# altair.net
KiCad netlist of a schematic drawn in EAGLE
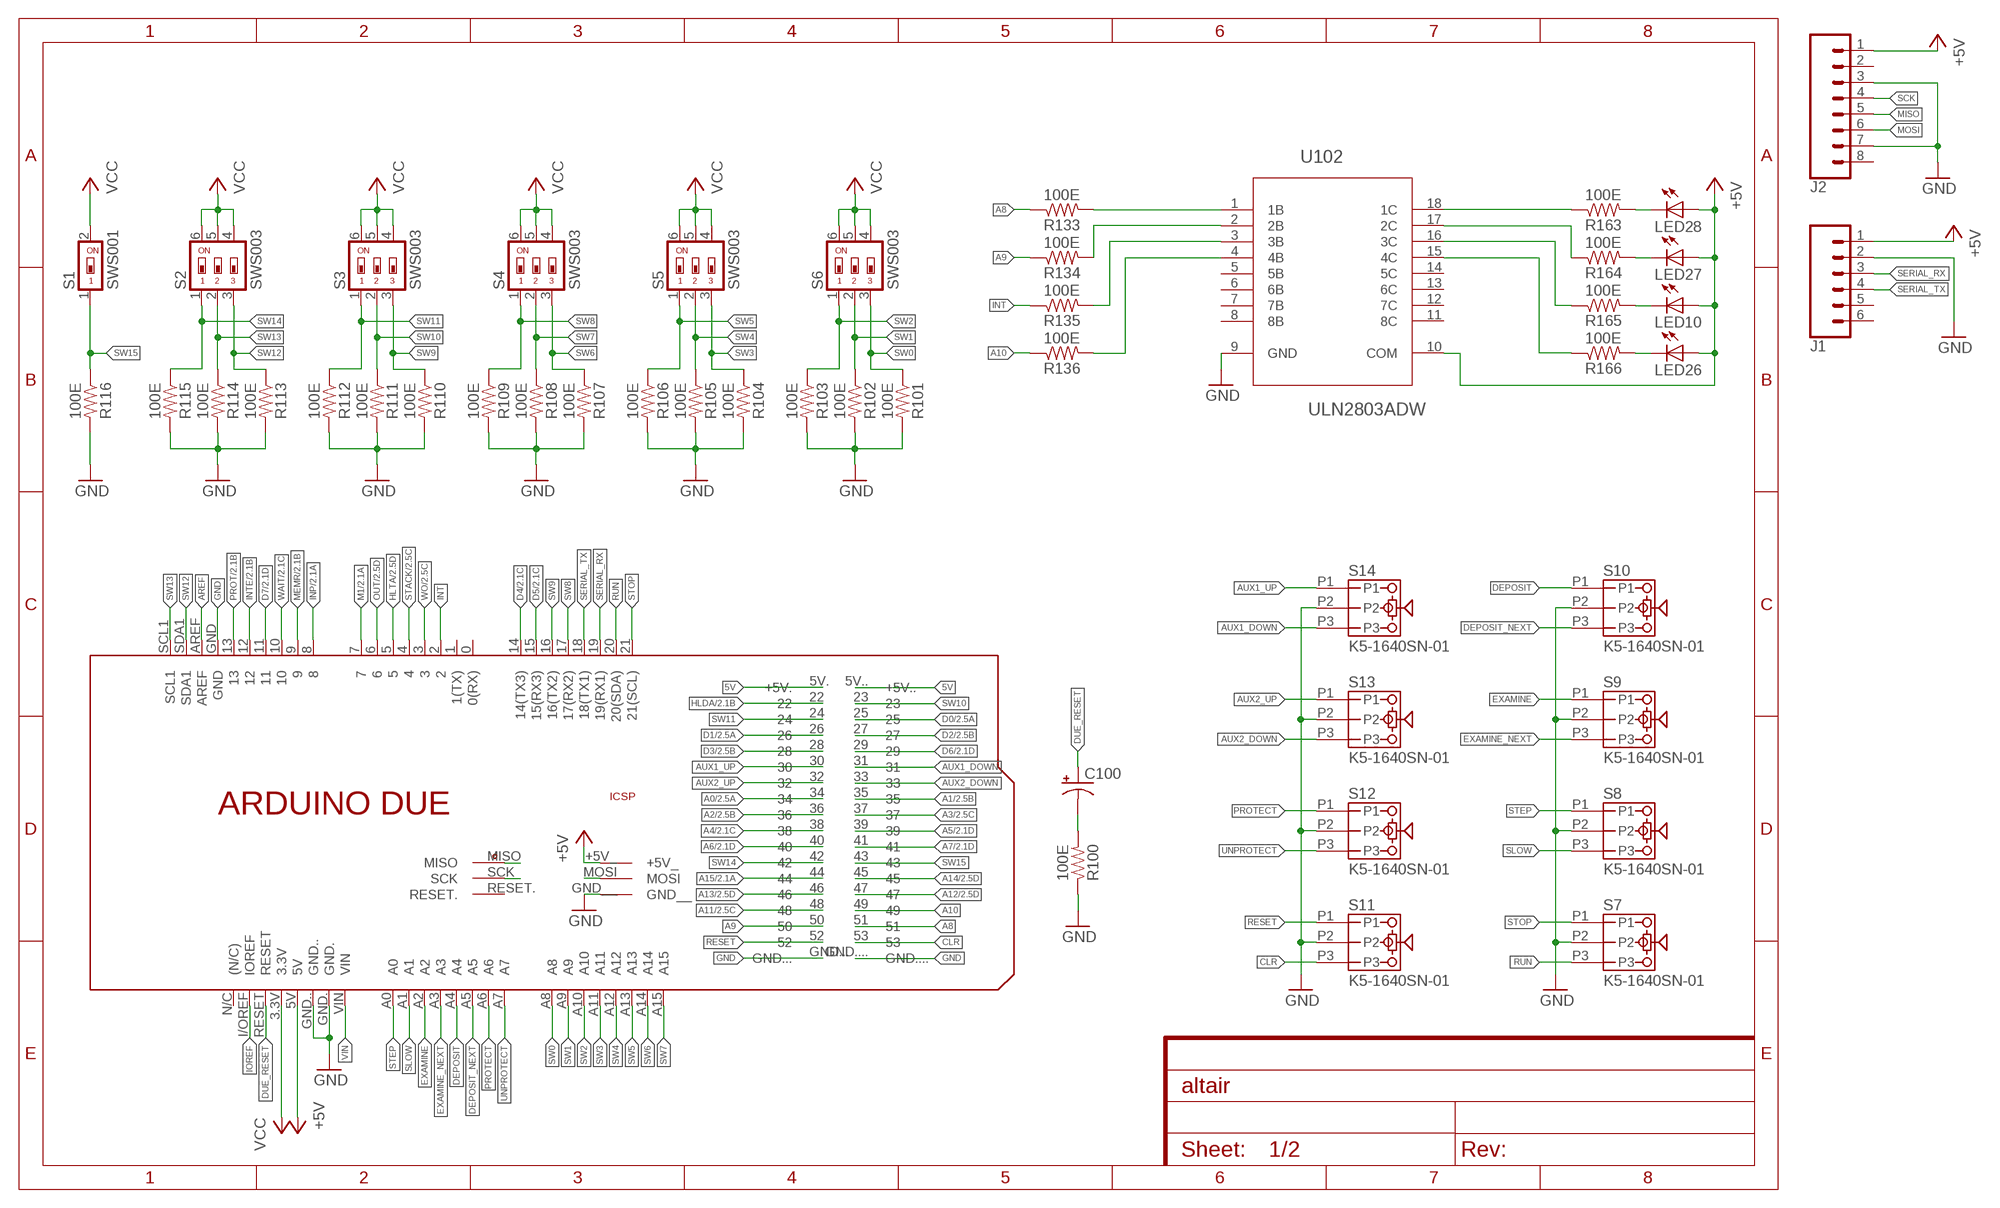
[diagram p0: schematic, sheet 1]
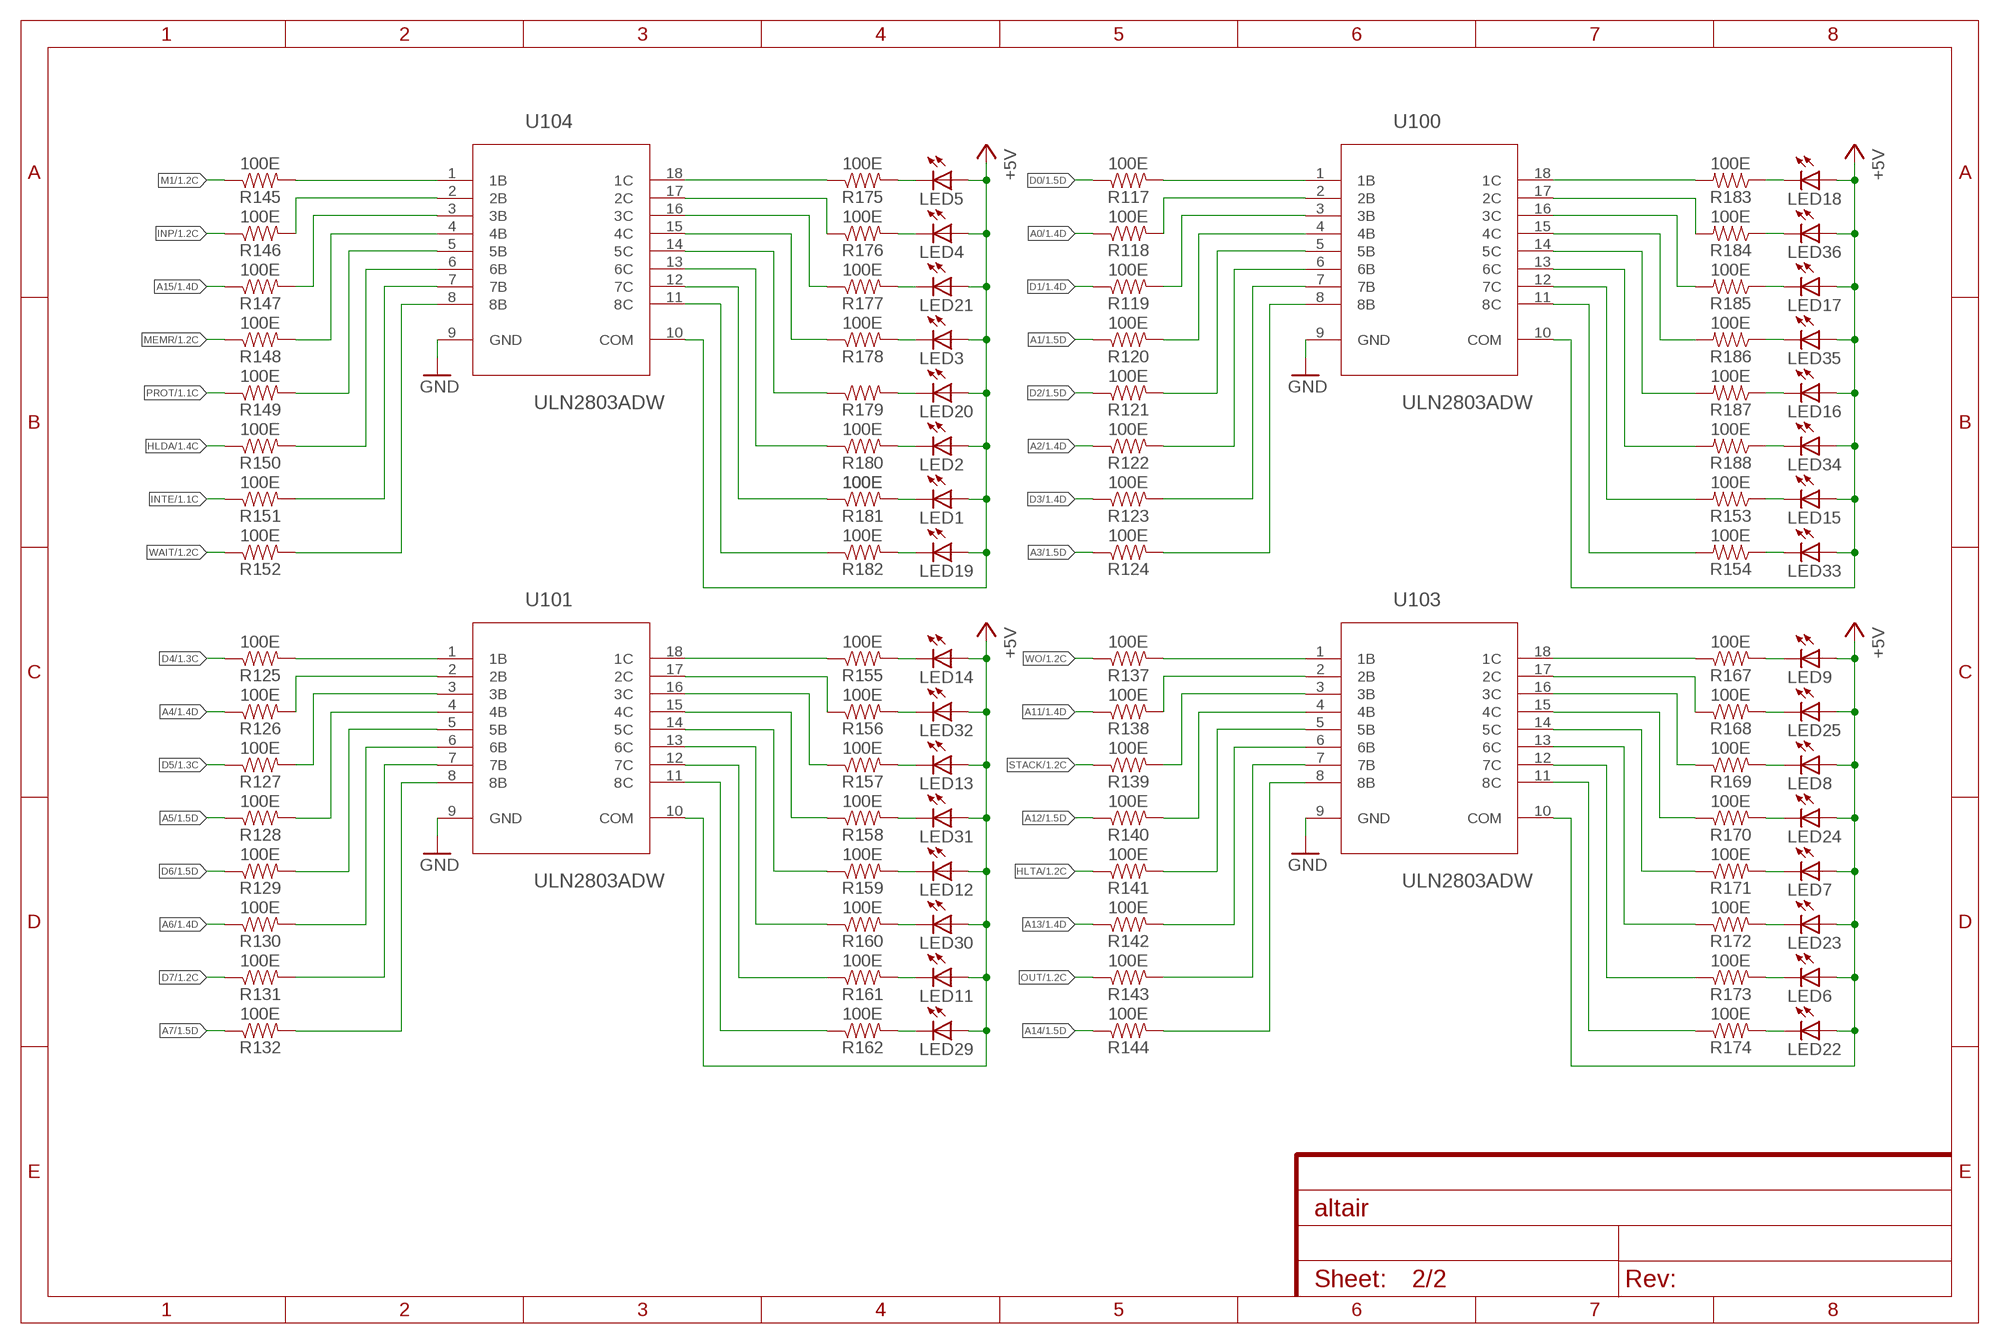
[diagram p1: schematic, sheet 2]

(export (version "E")
  (design (tool "Eeschema 10.0.6"))
  (components
    (comp (ref "C100")
      (value "CPOL-USD")
      (footprint "eagle-import:PANASONIC_D")
      (libsource (lib "eagle-import") (part "CPOL-USD"))
    )
    (comp (ref "J1")
      (value "CONN_06LOCK")
      (footprint "eagle-import:1X06_LOCK")
      (libsource (lib "eagle-import") (part "CONN_06LOCK"))
    )
    (comp (ref "J2")
      (value "CONN_08LOCK")
      (footprint "eagle-import:1X08_LOCK")
      (libsource (lib "eagle-import") (part "CONN_08LOCK"))
    )
    (comp (ref "LED10")
      (value "LEDCHIP-LED0805")
      (footprint "eagle-import:CHIP-LED0805")
      (libsource (lib "eagle-import") (part "LEDCHIP-LED0805"))
    )
    (comp (ref "LED26")
      (value "LEDCHIP-LED0805")
      (footprint "eagle-import:CHIP-LED0805")
      (libsource (lib "eagle-import") (part "LEDCHIP-LED0805"))
    )
    (comp (ref "LED27")
      (value "LEDCHIP-LED0805")
      (footprint "eagle-import:CHIP-LED0805")
      (libsource (lib "eagle-import") (part "LEDCHIP-LED0805"))
    )
    (comp (ref "LED28")
      (value "LEDCHIP-LED0805")
      (footprint "eagle-import:CHIP-LED0805")
      (libsource (lib "eagle-import") (part "LEDCHIP-LED0805"))
    )
    (comp (ref "PCB1")
      (value "ARDUINO_DUEARDUINO_DUE")
      (footprint "eagle-import:ARDUINO_MEGA2560")
      (libsource (lib "eagle-import") (part "ARDUINO_DUEARDUINO_DUE"))
    )
    (comp (ref "R100")
      (value "100E")
      (footprint "eagle-import:0805")
      (libsource (lib "eagle-import") (part "RESISTOR0805"))
    )
    (comp (ref "R101")
      (value "100E")
      (footprint "eagle-import:0805")
      (libsource (lib "eagle-import") (part "RESISTOR0805"))
    )
    (comp (ref "R102")
      (value "100E")
      (footprint "eagle-import:0805")
      (libsource (lib "eagle-import") (part "RESISTOR0805"))
    )
    (comp (ref "R103")
      (value "100E")
      (footprint "eagle-import:0805")
      (libsource (lib "eagle-import") (part "RESISTOR0805"))
    )
    (comp (ref "R104")
      (value "100E")
      (footprint "eagle-import:0805")
      (libsource (lib "eagle-import") (part "RESISTOR0805"))
    )
    (comp (ref "R105")
      (value "100E")
      (footprint "eagle-import:0805")
      (libsource (lib "eagle-import") (part "RESISTOR0805"))
    )
    (comp (ref "R106")
      (value "100E")
      (footprint "eagle-import:0805")
      (libsource (lib "eagle-import") (part "RESISTOR0805"))
    )
    (comp (ref "R107")
      (value "100E")
      (footprint "eagle-import:0805")
      (libsource (lib "eagle-import") (part "RESISTOR0805"))
    )
    (comp (ref "R108")
      (value "100E")
      (footprint "eagle-import:0805")
      (libsource (lib "eagle-import") (part "RESISTOR0805"))
    )
    (comp (ref "R109")
      (value "100E")
      (footprint "eagle-import:0805")
      (libsource (lib "eagle-import") (part "RESISTOR0805"))
    )
    (comp (ref "R110")
      (value "100E")
      (footprint "eagle-import:0805")
      (libsource (lib "eagle-import") (part "RESISTOR0805"))
    )
    (comp (ref "R111")
      (value "100E")
      (footprint "eagle-import:0805")
      (libsource (lib "eagle-import") (part "RESISTOR0805"))
    )
    (comp (ref "R112")
      (value "100E")
      (footprint "eagle-import:0805")
      (libsource (lib "eagle-import") (part "RESISTOR0805"))
    )
    (comp (ref "R113")
      (value "100E")
      (footprint "eagle-import:0805")
      (libsource (lib "eagle-import") (part "RESISTOR0805"))
    )
    (comp (ref "R114")
      (value "100E")
      (footprint "eagle-import:0805")
      (libsource (lib "eagle-import") (part "RESISTOR0805"))
    )
    (comp (ref "R115")
      (value "100E")
      (footprint "eagle-import:0805")
      (libsource (lib "eagle-import") (part "RESISTOR0805"))
    )
    (comp (ref "R116")
      (value "100E")
      (footprint "eagle-import:0805")
      (libsource (lib "eagle-import") (part "RESISTOR0805"))
    )
    (comp (ref "R133")
      (value "100E")
      (footprint "eagle-import:0805")
      (libsource (lib "eagle-import") (part "RESISTOR0805"))
    )
    (comp (ref "R134")
      (value "100E")
      (footprint "eagle-import:0805")
      (libsource (lib "eagle-import") (part "RESISTOR0805"))
    )
    (comp (ref "R135")
      (value "100E")
      (footprint "eagle-import:0805")
      (libsource (lib "eagle-import") (part "RESISTOR0805"))
    )
    (comp (ref "R136")
      (value "100E")
      (footprint "eagle-import:0805")
      (libsource (lib "eagle-import") (part "RESISTOR0805"))
    )
    (comp (ref "R163")
      (value "100E")
      (footprint "eagle-import:0805")
      (libsource (lib "eagle-import") (part "RESISTOR0805"))
    )
    (comp (ref "R164")
      (value "100E")
      (footprint "eagle-import:0805")
      (libsource (lib "eagle-import") (part "RESISTOR0805"))
    )
    (comp (ref "R165")
      (value "100E")
      (footprint "eagle-import:0805")
      (libsource (lib "eagle-import") (part "RESISTOR0805"))
    )
    (comp (ref "R166")
      (value "100E")
      (footprint "eagle-import:0805")
      (libsource (lib "eagle-import") (part "RESISTOR0805"))
    )
    (comp (ref "S1")
      (value "SWS001")
      (footprint "eagle-import:SMS-001")
      (libsource (lib "eagle-import") (part "SWS001"))
    )
    (comp (ref "S2")
      (value "SWS003")
      (footprint "eagle-import:SMS-003")
      (libsource (lib "eagle-import") (part "SWS003"))
    )
    (comp (ref "S3")
      (value "SWS003")
      (footprint "eagle-import:SMS-003")
      (libsource (lib "eagle-import") (part "SWS003"))
    )
    (comp (ref "S4")
      (value "SWS003")
      (footprint "eagle-import:SMS-003")
      (libsource (lib "eagle-import") (part "SWS003"))
    )
    (comp (ref "S5")
      (value "SWS003")
      (footprint "eagle-import:SMS-003")
      (libsource (lib "eagle-import") (part "SWS003"))
    )
    (comp (ref "S6")
      (value "SWS003")
      (footprint "eagle-import:SMS-003")
      (libsource (lib "eagle-import") (part "SWS003"))
    )
    (comp (ref "S7")
      (value "K5-1640SN-01")
      (footprint "eagle-import:K5-1640SN-01")
      (libsource (lib "eagle-import") (part "K5-1640SN-01"))
    )
    (comp (ref "S8")
      (value "K5-1640SN-01")
      (footprint "eagle-import:K5-1640SN-01")
      (libsource (lib "eagle-import") (part "K5-1640SN-01"))
    )
    (comp (ref "S9")
      (value "K5-1640SN-01")
      (footprint "eagle-import:K5-1640SN-01")
      (libsource (lib "eagle-import") (part "K5-1640SN-01"))
    )
    (comp (ref "S10")
      (value "K5-1640SN-01")
      (footprint "eagle-import:K5-1640SN-01")
      (libsource (lib "eagle-import") (part "K5-1640SN-01"))
    )
    (comp (ref "S11")
      (value "K5-1640SN-01")
      (footprint "eagle-import:K5-1640SN-01")
      (libsource (lib "eagle-import") (part "K5-1640SN-01"))
    )
    (comp (ref "S12")
      (value "K5-1640SN-01")
      (footprint "eagle-import:K5-1640SN-01")
      (libsource (lib "eagle-import") (part "K5-1640SN-01"))
    )
    (comp (ref "S13")
      (value "K5-1640SN-01")
      (footprint "eagle-import:K5-1640SN-01")
      (libsource (lib "eagle-import") (part "K5-1640SN-01"))
    )
    (comp (ref "S14")
      (value "K5-1640SN-01")
      (footprint "eagle-import:K5-1640SN-01")
      (libsource (lib "eagle-import") (part "K5-1640SN-01"))
    )
    (comp (ref "U102")
      (value "ULN2803ADW")
      (footprint "eagle-import:SOIC127P1030X265-18N")
      (libsource (lib "eagle-import") (part "ULN2803ADW"))
    )
    (comp (ref "LED1")
      (value "LEDCHIP-LED0805")
      (footprint "eagle-import:CHIP-LED0805")
      (libsource (lib "eagle-import") (part "LEDCHIP-LED0805"))
    )
    (comp (ref "LED2")
      (value "LEDCHIP-LED0805")
      (footprint "eagle-import:CHIP-LED0805")
      (libsource (lib "eagle-import") (part "LEDCHIP-LED0805"))
    )
    (comp (ref "LED3")
      (value "LEDCHIP-LED0805")
      (footprint "eagle-import:CHIP-LED0805")
      (libsource (lib "eagle-import") (part "LEDCHIP-LED0805"))
    )
    (comp (ref "LED4")
      (value "LEDCHIP-LED0805")
      (footprint "eagle-import:CHIP-LED0805")
      (libsource (lib "eagle-import") (part "LEDCHIP-LED0805"))
    )
    (comp (ref "LED5")
      (value "LEDCHIP-LED0805")
      (footprint "eagle-import:CHIP-LED0805")
      (libsource (lib "eagle-import") (part "LEDCHIP-LED0805"))
    )
    (comp (ref "LED6")
      (value "LEDCHIP-LED0805")
      (footprint "eagle-import:CHIP-LED0805")
      (libsource (lib "eagle-import") (part "LEDCHIP-LED0805"))
    )
    (comp (ref "LED7")
      (value "LEDCHIP-LED0805")
      (footprint "eagle-import:CHIP-LED0805")
      (libsource (lib "eagle-import") (part "LEDCHIP-LED0805"))
    )
    (comp (ref "LED8")
      (value "LEDCHIP-LED0805")
      (footprint "eagle-import:CHIP-LED0805")
      (libsource (lib "eagle-import") (part "LEDCHIP-LED0805"))
    )
    (comp (ref "LED9")
      (value "LEDCHIP-LED0805")
      (footprint "eagle-import:CHIP-LED0805")
      (libsource (lib "eagle-import") (part "LEDCHIP-LED0805"))
    )
    (comp (ref "LED11")
      (value "LEDCHIP-LED0805")
      (footprint "eagle-import:CHIP-LED0805")
      (libsource (lib "eagle-import") (part "LEDCHIP-LED0805"))
    )
    (comp (ref "LED12")
      (value "LEDCHIP-LED0805")
      (footprint "eagle-import:CHIP-LED0805")
      (libsource (lib "eagle-import") (part "LEDCHIP-LED0805"))
    )
    (comp (ref "LED13")
      (value "LEDCHIP-LED0805")
      (footprint "eagle-import:CHIP-LED0805")
      (libsource (lib "eagle-import") (part "LEDCHIP-LED0805"))
    )
    (comp (ref "LED14")
      (value "LEDCHIP-LED0805")
      (footprint "eagle-import:CHIP-LED0805")
      (libsource (lib "eagle-import") (part "LEDCHIP-LED0805"))
    )
    (comp (ref "LED15")
      (value "LEDCHIP-LED0805")
      (footprint "eagle-import:CHIP-LED0805")
      (libsource (lib "eagle-import") (part "LEDCHIP-LED0805"))
    )
    (comp (ref "LED16")
      (value "LEDCHIP-LED0805")
      (footprint "eagle-import:CHIP-LED0805")
      (libsource (lib "eagle-import") (part "LEDCHIP-LED0805"))
    )
    (comp (ref "LED17")
      (value "LEDCHIP-LED0805")
      (footprint "eagle-import:CHIP-LED0805")
      (libsource (lib "eagle-import") (part "LEDCHIP-LED0805"))
    )
    (comp (ref "LED18")
      (value "LEDCHIP-LED0805")
      (footprint "eagle-import:CHIP-LED0805")
      (libsource (lib "eagle-import") (part "LEDCHIP-LED0805"))
    )
    (comp (ref "LED19")
      (value "LEDCHIP-LED0805")
      (footprint "eagle-import:CHIP-LED0805")
      (libsource (lib "eagle-import") (part "LEDCHIP-LED0805"))
    )
    (comp (ref "LED20")
      (value "LEDCHIP-LED0805")
      (footprint "eagle-import:CHIP-LED0805")
      (libsource (lib "eagle-import") (part "LEDCHIP-LED0805"))
    )
    (comp (ref "LED21")
      (value "LEDCHIP-LED0805")
      (footprint "eagle-import:CHIP-LED0805")
      (libsource (lib "eagle-import") (part "LEDCHIP-LED0805"))
    )
    (comp (ref "LED22")
      (value "LEDCHIP-LED0805")
      (footprint "eagle-import:CHIP-LED0805")
      (libsource (lib "eagle-import") (part "LEDCHIP-LED0805"))
    )
    (comp (ref "LED23")
      (value "LEDCHIP-LED0805")
      (footprint "eagle-import:CHIP-LED0805")
      (libsource (lib "eagle-import") (part "LEDCHIP-LED0805"))
    )
    (comp (ref "LED24")
      (value "LEDCHIP-LED0805")
      (footprint "eagle-import:CHIP-LED0805")
      (libsource (lib "eagle-import") (part "LEDCHIP-LED0805"))
    )
    (comp (ref "LED25")
      (value "LEDCHIP-LED0805")
      (footprint "eagle-import:CHIP-LED0805")
      (libsource (lib "eagle-import") (part "LEDCHIP-LED0805"))
    )
    (comp (ref "LED29")
      (value "LEDCHIP-LED0805")
      (footprint "eagle-import:CHIP-LED0805")
      (libsource (lib "eagle-import") (part "LEDCHIP-LED0805"))
    )
    (comp (ref "LED30")
      (value "LEDCHIP-LED0805")
      (footprint "eagle-import:CHIP-LED0805")
      (libsource (lib "eagle-import") (part "LEDCHIP-LED0805"))
    )
    (comp (ref "LED31")
      (value "LEDCHIP-LED0805")
      (footprint "eagle-import:CHIP-LED0805")
      (libsource (lib "eagle-import") (part "LEDCHIP-LED0805"))
    )
    (comp (ref "LED32")
      (value "LEDCHIP-LED0805")
      (footprint "eagle-import:CHIP-LED0805")
      (libsource (lib "eagle-import") (part "LEDCHIP-LED0805"))
    )
    (comp (ref "LED33")
      (value "LEDCHIP-LED0805")
      (footprint "eagle-import:CHIP-LED0805")
      (libsource (lib "eagle-import") (part "LEDCHIP-LED0805"))
    )
    (comp (ref "LED34")
      (value "LEDCHIP-LED0805")
      (footprint "eagle-import:CHIP-LED0805")
      (libsource (lib "eagle-import") (part "LEDCHIP-LED0805"))
    )
    (comp (ref "LED35")
      (value "LEDCHIP-LED0805")
      (footprint "eagle-import:CHIP-LED0805")
      (libsource (lib "eagle-import") (part "LEDCHIP-LED0805"))
    )
    (comp (ref "LED36")
      (value "LEDCHIP-LED0805")
      (footprint "eagle-import:CHIP-LED0805")
      (libsource (lib "eagle-import") (part "LEDCHIP-LED0805"))
    )
    (comp (ref "R117")
      (value "100E")
      (footprint "eagle-import:0805")
      (libsource (lib "eagle-import") (part "RESISTOR0805"))
    )
    (comp (ref "R118")
      (value "100E")
      (footprint "eagle-import:0805")
      (libsource (lib "eagle-import") (part "RESISTOR0805"))
    )
    (comp (ref "R119")
      (value "100E")
      (footprint "eagle-import:0805")
      (libsource (lib "eagle-import") (part "RESISTOR0805"))
    )
    (comp (ref "R120")
      (value "100E")
      (footprint "eagle-import:0805")
      (libsource (lib "eagle-import") (part "RESISTOR0805"))
    )
    (comp (ref "R121")
      (value "100E")
      (footprint "eagle-import:0805")
      (libsource (lib "eagle-import") (part "RESISTOR0805"))
    )
    (comp (ref "R122")
      (value "100E")
      (footprint "eagle-import:0805")
      (libsource (lib "eagle-import") (part "RESISTOR0805"))
    )
    (comp (ref "R123")
      (value "100E")
      (footprint "eagle-import:0805")
      (libsource (lib "eagle-import") (part "RESISTOR0805"))
    )
    (comp (ref "R124")
      (value "100E")
      (footprint "eagle-import:0805")
      (libsource (lib "eagle-import") (part "RESISTOR0805"))
    )
    (comp (ref "R125")
      (value "100E")
      (footprint "eagle-import:0805")
      (libsource (lib "eagle-import") (part "RESISTOR0805"))
    )
    (comp (ref "R126")
      (value "100E")
      (footprint "eagle-import:0805")
      (libsource (lib "eagle-import") (part "RESISTOR0805"))
    )
    (comp (ref "R127")
      (value "100E")
      (footprint "eagle-import:0805")
      (libsource (lib "eagle-import") (part "RESISTOR0805"))
    )
    (comp (ref "R128")
      (value "100E")
      (footprint "eagle-import:0805")
      (libsource (lib "eagle-import") (part "RESISTOR0805"))
    )
    (comp (ref "R129")
      (value "100E")
      (footprint "eagle-import:0805")
      (libsource (lib "eagle-import") (part "RESISTOR0805"))
    )
    (comp (ref "R130")
      (value "100E")
      (footprint "eagle-import:0805")
      (libsource (lib "eagle-import") (part "RESISTOR0805"))
    )
    (comp (ref "R131")
      (value "100E")
      (footprint "eagle-import:0805")
      (libsource (lib "eagle-import") (part "RESISTOR0805"))
    )
    (comp (ref "R132")
      (value "100E")
      (footprint "eagle-import:0805")
      (libsource (lib "eagle-import") (part "RESISTOR0805"))
    )
    (comp (ref "R137")
      (value "100E")
      (footprint "eagle-import:0805")
      (libsource (lib "eagle-import") (part "RESISTOR0805"))
    )
    (comp (ref "R138")
      (value "100E")
      (footprint "eagle-import:0805")
      (libsource (lib "eagle-import") (part "RESISTOR0805"))
    )
    (comp (ref "R139")
      (value "100E")
      (footprint "eagle-import:0805")
      (libsource (lib "eagle-import") (part "RESISTOR0805"))
    )
    (comp (ref "R140")
      (value "100E")
      (footprint "eagle-import:0805")
      (libsource (lib "eagle-import") (part "RESISTOR0805"))
    )
    (comp (ref "R141")
      (value "100E")
      (footprint "eagle-import:0805")
      (libsource (lib "eagle-import") (part "RESISTOR0805"))
    )
    (comp (ref "R142")
      (value "100E")
      (footprint "eagle-import:0805")
      (libsource (lib "eagle-import") (part "RESISTOR0805"))
    )
    (comp (ref "R143")
      (value "100E")
      (footprint "eagle-import:0805")
      (libsource (lib "eagle-import") (part "RESISTOR0805"))
    )
    (comp (ref "R144")
      (value "100E")
      (footprint "eagle-import:0805")
      (libsource (lib "eagle-import") (part "RESISTOR0805"))
    )
    (comp (ref "R145")
      (value "100E")
      (footprint "eagle-import:0805")
      (libsource (lib "eagle-import") (part "RESISTOR0805"))
    )
    (comp (ref "R146")
      (value "100E")
      (footprint "eagle-import:0805")
      (libsource (lib "eagle-import") (part "RESISTOR0805"))
    )
    (comp (ref "R147")
      (value "100E")
      (footprint "eagle-import:0805")
      (libsource (lib "eagle-import") (part "RESISTOR0805"))
    )
    (comp (ref "R148")
      (value "100E")
      (footprint "eagle-import:0805")
      (libsource (lib "eagle-import") (part "RESISTOR0805"))
    )
    (comp (ref "R149")
      (value "100E")
      (footprint "eagle-import:0805")
      (libsource (lib "eagle-import") (part "RESISTOR0805"))
    )
    (comp (ref "R150")
      (value "100E")
      (footprint "eagle-import:0805")
      (libsource (lib "eagle-import") (part "RESISTOR0805"))
    )
    (comp (ref "R151")
      (value "100E")
      (footprint "eagle-import:0805")
      (libsource (lib "eagle-import") (part "RESISTOR0805"))
    )
    (comp (ref "R152")
      (value "100E")
      (footprint "eagle-import:0805")
      (libsource (lib "eagle-import") (part "RESISTOR0805"))
    )
    (comp (ref "R153")
      (value "100E")
      (footprint "eagle-import:0805")
      (libsource (lib "eagle-import") (part "RESISTOR0805"))
    )
    (comp (ref "R154")
      (value "100E")
      (footprint "eagle-import:0805")
      (libsource (lib "eagle-import") (part "RESISTOR0805"))
    )
    (comp (ref "R155")
      (value "100E")
      (footprint "eagle-import:0805")
      (libsource (lib "eagle-import") (part "RESISTOR0805"))
    )
    (comp (ref "R156")
      (value "100E")
      (footprint "eagle-import:0805")
      (libsource (lib "eagle-import") (part "RESISTOR0805"))
    )
    (comp (ref "R157")
      (value "100E")
      (footprint "eagle-import:0805")
      (libsource (lib "eagle-import") (part "RESISTOR0805"))
    )
    (comp (ref "R158")
      (value "100E")
      (footprint "eagle-import:0805")
      (libsource (lib "eagle-import") (part "RESISTOR0805"))
    )
    (comp (ref "R159")
      (value "100E")
      (footprint "eagle-import:0805")
      (libsource (lib "eagle-import") (part "RESISTOR0805"))
    )
    (comp (ref "R160")
      (value "100E")
      (footprint "eagle-import:0805")
      (libsource (lib "eagle-import") (part "RESISTOR0805"))
    )
    (comp (ref "R161")
      (value "100E")
      (footprint "eagle-import:0805")
      (libsource (lib "eagle-import") (part "RESISTOR0805"))
    )
    (comp (ref "R162")
      (value "100E")
      (footprint "eagle-import:0805")
      (libsource (lib "eagle-import") (part "RESISTOR0805"))
    )
    (comp (ref "R167")
      (value "100E")
      (footprint "eagle-import:0805")
      (libsource (lib "eagle-import") (part "RESISTOR0805"))
    )
    (comp (ref "R168")
      (value "100E")
      (footprint "eagle-import:0805")
      (libsource (lib "eagle-import") (part "RESISTOR0805"))
    )
    (comp (ref "R169")
      (value "100E")
      (footprint "eagle-import:0805")
      (libsource (lib "eagle-import") (part "RESISTOR0805"))
    )
    (comp (ref "R170")
      (value "100E")
      (footprint "eagle-import:0805")
      (libsource (lib "eagle-import") (part "RESISTOR0805"))
    )
    (comp (ref "R171")
      (value "100E")
      (footprint "eagle-import:0805")
      (libsource (lib "eagle-import") (part "RESISTOR0805"))
    )
    (comp (ref "R172")
      (value "100E")
      (footprint "eagle-import:0805")
      (libsource (lib "eagle-import") (part "RESISTOR0805"))
    )
    (comp (ref "R173")
      (value "100E")
      (footprint "eagle-import:0805")
      (libsource (lib "eagle-import") (part "RESISTOR0805"))
    )
    (comp (ref "R174")
      (value "100E")
      (footprint "eagle-import:0805")
      (libsource (lib "eagle-import") (part "RESISTOR0805"))
    )
    (comp (ref "R175")
      (value "100E")
      (footprint "eagle-import:0805")
      (libsource (lib "eagle-import") (part "RESISTOR0805"))
    )
    (comp (ref "R176")
      (value "100E")
      (footprint "eagle-import:0805")
      (libsource (lib "eagle-import") (part "RESISTOR0805"))
    )
    (comp (ref "R177")
      (value "100E")
      (footprint "eagle-import:0805")
      (libsource (lib "eagle-import") (part "RESISTOR0805"))
    )
    (comp (ref "R178")
      (value "100E")
      (footprint "eagle-import:0805")
      (libsource (lib "eagle-import") (part "RESISTOR0805"))
    )
    (comp (ref "R179")
      (value "100E")
      (footprint "eagle-import:0805")
      (libsource (lib "eagle-import") (part "RESISTOR0805"))
    )
    (comp (ref "R180")
      (value "100E")
      (footprint "eagle-import:0805")
      (libsource (lib "eagle-import") (part "RESISTOR0805"))
    )
    (comp (ref "R181")
      (value "100E")
      (footprint "eagle-import:0805")
      (libsource (lib "eagle-import") (part "RESISTOR0805"))
    )
    (comp (ref "R182")
      (value "100E")
      (footprint "eagle-import:0805")
      (libsource (lib "eagle-import") (part "RESISTOR0805"))
    )
    (comp (ref "R183")
      (value "100E")
      (footprint "eagle-import:0805")
      (libsource (lib "eagle-import") (part "RESISTOR0805"))
    )
    (comp (ref "R184")
      (value "100E")
      (footprint "eagle-import:0805")
      (libsource (lib "eagle-import") (part "RESISTOR0805"))
    )
    (comp (ref "R185")
      (value "100E")
      (footprint "eagle-import:0805")
      (libsource (lib "eagle-import") (part "RESISTOR0805"))
    )
    (comp (ref "R186")
      (value "100E")
      (footprint "eagle-import:0805")
      (libsource (lib "eagle-import") (part "RESISTOR0805"))
    )
    (comp (ref "R187")
      (value "100E")
      (footprint "eagle-import:0805")
      (libsource (lib "eagle-import") (part "RESISTOR0805"))
    )
    (comp (ref "R188")
      (value "100E")
      (footprint "eagle-import:0805")
      (libsource (lib "eagle-import") (part "RESISTOR0805"))
    )
    (comp (ref "U100")
      (value "ULN2803ADW")
      (footprint "eagle-import:SOIC127P1030X265-18N")
      (libsource (lib "eagle-import") (part "ULN2803ADW"))
    )
    (comp (ref "U101")
      (value "ULN2803ADW")
      (footprint "eagle-import:SOIC127P1030X265-18N")
      (libsource (lib "eagle-import") (part "ULN2803ADW"))
    )
    (comp (ref "U103")
      (value "ULN2803ADW")
      (footprint "eagle-import:SOIC127P1030X265-18N")
      (libsource (lib "eagle-import") (part "ULN2803ADW"))
    )
    (comp (ref "U104")
      (value "ULN2803ADW")
      (footprint "eagle-import:SOIC127P1030X265-18N")
      (libsource (lib "eagle-import") (part "ULN2803ADW"))
    )
  )
  (nets
    (net (code "1") (name "+5V") (class "Default")
      (node (ref "J1") (pin "1") (pinfunction "1_1") (pintype "passive"))
      (node (ref "J2") (pin "1") (pinfunction "1_1") (pintype "passive"))
      (node (ref "LED1") (pin "A") (pinfunction "A_A") (pintype "passive"))
      (node (ref "LED10") (pin "A") (pinfunction "A_A") (pintype "passive"))
      (node (ref "LED11") (pin "A") (pinfunction "A_A") (pintype "passive"))
      (node (ref "LED12") (pin "A") (pinfunction "A_A") (pintype "passive"))
      (node (ref "LED13") (pin "A") (pinfunction "A_A") (pintype "passive"))
      (node (ref "LED14") (pin "A") (pinfunction "A_A") (pintype "passive"))
      (node (ref "LED15") (pin "A") (pinfunction "A_A") (pintype "passive"))
      (node (ref "LED16") (pin "A") (pinfunction "A_A") (pintype "passive"))
      (node (ref "LED17") (pin "A") (pinfunction "A_A") (pintype "passive"))
      (node (ref "LED18") (pin "A") (pinfunction "A_A") (pintype "passive"))
      (node (ref "LED19") (pin "A") (pinfunction "A_A") (pintype "passive"))
      (node (ref "LED2") (pin "A") (pinfunction "A_A") (pintype "passive"))
      (node (ref "LED20") (pin "A") (pinfunction "A_A") (pintype "passive"))
      (node (ref "LED21") (pin "A") (pinfunction "A_A") (pintype "passive"))
      (node (ref "LED22") (pin "A") (pinfunction "A_A") (pintype "passive"))
      (node (ref "LED23") (pin "A") (pinfunction "A_A") (pintype "passive"))
      (node (ref "LED24") (pin "A") (pinfunction "A_A") (pintype "passive"))
      (node (ref "LED25") (pin "A") (pinfunction "A_A") (pintype "passive"))
      (node (ref "LED26") (pin "A") (pinfunction "A_A") (pintype "passive"))
      (node (ref "LED27") (pin "A") (pinfunction "A_A") (pintype "passive"))
      (node (ref "LED28") (pin "A") (pinfunction "A_A") (pintype "passive"))
      (node (ref "LED29") (pin "A") (pinfunction "A_A") (pintype "passive"))
      (node (ref "LED3") (pin "A") (pinfunction "A_A") (pintype "passive"))
      (node (ref "LED30") (pin "A") (pinfunction "A_A") (pintype "passive"))
      (node (ref "LED31") (pin "A") (pinfunction "A_A") (pintype "passive"))
      (node (ref "LED32") (pin "A") (pinfunction "A_A") (pintype "passive"))
      (node (ref "LED33") (pin "A") (pinfunction "A_A") (pintype "passive"))
      (node (ref "LED34") (pin "A") (pinfunction "A_A") (pintype "passive"))
      (node (ref "LED35") (pin "A") (pinfunction "A_A") (pintype "passive"))
      (node (ref "LED36") (pin "A") (pinfunction "A_A") (pintype "passive"))
      (node (ref "LED4") (pin "A") (pinfunction "A_A") (pintype "passive"))
      (node (ref "LED5") (pin "A") (pinfunction "A_A") (pintype "passive"))
      (node (ref "LED6") (pin "A") (pinfunction "A_A") (pintype "passive"))
      (node (ref "LED7") (pin "A") (pinfunction "A_A") (pintype "passive"))
      (node (ref "LED8") (pin "A") (pinfunction "A_A") (pintype "passive"))
      (node (ref "LED9") (pin "A") (pinfunction "A_A") (pintype "passive"))
      (node (ref "PCB1") (pin "+5V_") (pinfunction "+5V__+5V_") (pintype "bidirectional"))
      (node (ref "PCB1") (pin "5V") (pinfunction "5V_5V") (pintype "bidirectional"))
      (node (ref "U100") (pin "10") (pinfunction "COM_10") (pintype "output"))
      (node (ref "U101") (pin "10") (pinfunction "COM_10") (pintype "output"))
      (node (ref "U102") (pin "10") (pinfunction "COM_10") (pintype "output"))
      (node (ref "U103") (pin "10") (pinfunction "COM_10") (pintype "output"))
      (node (ref "U104") (pin "10") (pinfunction "COM_10") (pintype "output"))
    )
    (net (code "2") (name "5V") (class "Default")
      (node (ref "PCB1") (pin "5V.") (pinfunction "+5V._5V.") (pintype "bidirectional"))
      (node (ref "PCB1") (pin "5V..") (pinfunction "+5V.._5V..") (pintype "bidirectional"))
    )
    (net (code "3") (name "A0") (class "Default")
      (node (ref "PCB1") (pin "34") (pinfunction "34_34") (pintype "bidirectional"))
      (node (ref "R118") (pin "1") (pinfunction "1_1") (pintype "passive"))
    )
    (net (code "4") (name "A1") (class "Default")
      (node (ref "PCB1") (pin "35") (pinfunction "35_35") (pintype "bidirectional"))
      (node (ref "R120") (pin "1") (pinfunction "1_1") (pintype "passive"))
    )
    (net (code "5") (name "A2") (class "Default")
      (node (ref "PCB1") (pin "36") (pinfunction "36_36") (pintype "bidirectional"))
      (node (ref "R122") (pin "1") (pinfunction "1_1") (pintype "passive"))
    )
    (net (code "6") (name "A3") (class "Default")
      (node (ref "PCB1") (pin "37") (pinfunction "37_37") (pintype "bidirectional"))
      (node (ref "R124") (pin "1") (pinfunction "1_1") (pintype "passive"))
    )
    (net (code "7") (name "A4") (class "Default")
      (node (ref "PCB1") (pin "38") (pinfunction "38_38") (pintype "bidirectional"))
      (node (ref "R126") (pin "1") (pinfunction "1_1") (pintype "passive"))
    )
    (net (code "8") (name "A5") (class "Default")
      (node (ref "PCB1") (pin "39") (pinfunction "39_39") (pintype "bidirectional"))
      (node (ref "R128") (pin "1") (pinfunction "1_1") (pintype "passive"))
    )
    (net (code "9") (name "A6") (class "Default")
      (node (ref "PCB1") (pin "40") (pinfunction "40_40") (pintype "bidirectional"))
      (node (ref "R130") (pin "1") (pinfunction "1_1") (pintype "passive"))
    )
    (net (code "10") (name "A7") (class "Default")
      (node (ref "PCB1") (pin "41") (pinfunction "41_41") (pintype "bidirectional"))
      (node (ref "R132") (pin "1") (pinfunction "1_1") (pintype "passive"))
    )
    (net (code "11") (name "A8") (class "Default")
      (node (ref "PCB1") (pin "51") (pinfunction "51_51") (pintype "bidirectional"))
      (node (ref "R133") (pin "1") (pinfunction "1_1") (pintype "passive"))
    )
    (net (code "12") (name "A9") (class "Default")
      (node (ref "PCB1") (pin "50") (pinfunction "50_50") (pintype "bidirectional"))
      (node (ref "R134") (pin "1") (pinfunction "1_1") (pintype "passive"))
    )
    (net (code "13") (name "A10") (class "Default")
      (node (ref "PCB1") (pin "49") (pinfunction "49_49") (pintype "bidirectional"))
      (node (ref "R136") (pin "1") (pinfunction "1_1") (pintype "passive"))
    )
    (net (code "14") (name "A11") (class "Default")
      (node (ref "PCB1") (pin "48") (pinfunction "48_48") (pintype "bidirectional"))
      (node (ref "R138") (pin "1") (pinfunction "1_1") (pintype "passive"))
    )
    (net (code "15") (name "A12") (class "Default")
      (node (ref "PCB1") (pin "47") (pinfunction "47_47") (pintype "bidirectional"))
      (node (ref "R140") (pin "1") (pinfunction "1_1") (pintype "passive"))
    )
    (net (code "16") (name "A13") (class "Default")
      (node (ref "PCB1") (pin "46") (pinfunction "46_46") (pintype "bidirectional"))
      (node (ref "R142") (pin "1") (pinfunction "1_1") (pintype "passive"))
    )
    (net (code "17") (name "A14") (class "Default")
      (node (ref "PCB1") (pin "45") (pinfunction "45_45") (pintype "bidirectional"))
      (node (ref "R144") (pin "1") (pinfunction "1_1") (pintype "passive"))
    )
    (net (code "18") (name "A15") (class "Default")
      (node (ref "PCB1") (pin "44") (pinfunction "44_44") (pintype "bidirectional"))
      (node (ref "R147") (pin "1") (pinfunction "1_1") (pintype "passive"))
    )
    (net (code "19") (name "AREF") (class "Default")
      (node (ref "PCB1") (pin "AREF") (pinfunction "AREF_AREF") (pintype "bidirectional"))
    )
    (net (code "20") (name "AUX1_DOWN") (class "Default")
      (node (ref "PCB1") (pin "31") (pinfunction "31_31") (pintype "bidirectional"))
      (node (ref "S14") (pin "P3") (pinfunction "P3_P3") (pintype "bidirectional"))
    )
    (net (code "21") (name "AUX1_UP") (class "Default")
      (node (ref "PCB1") (pin "30") (pinfunction "30_30") (pintype "bidirectional"))
      (node (ref "S14") (pin "P1") (pinfunction "P1_P1") (pintype "bidirectional"))
    )
    (net (code "22") (name "AUX2_DOWN") (class "Default")
      (node (ref "PCB1") (pin "33") (pinfunction "33_33") (pintype "bidirectional"))
      (node (ref "S13") (pin "P3") (pinfunction "P3_P3") (pintype "bidirectional"))
    )
    (net (code "23") (name "AUX2_UP") (class "Default")
      (node (ref "PCB1") (pin "32") (pinfunction "32_32") (pintype "bidirectional"))
      (node (ref "S13") (pin "P1") (pinfunction "P1_P1") (pintype "bidirectional"))
    )
    (net (code "24") (name "CLR") (class "Default")
      (node (ref "PCB1") (pin "53") (pinfunction "53_53") (pintype "bidirectional"))
      (node (ref "S11") (pin "P3") (pinfunction "P3_P3") (pintype "bidirectional"))
    )
    (net (code "25") (name "D0") (class "Default")
      (node (ref "PCB1") (pin "25") (pinfunction "25_25") (pintype "bidirectional"))
      (node (ref "R117") (pin "1") (pinfunction "1_1") (pintype "passive"))
    )
    (net (code "26") (name "D1") (class "Default")
      (node (ref "PCB1") (pin "26") (pinfunction "26_26") (pintype "bidirectional"))
      (node (ref "R119") (pin "1") (pinfunction "1_1") (pintype "passive"))
    )
    (net (code "27") (name "D2") (class "Default")
      (node (ref "PCB1") (pin "27") (pinfunction "27_27") (pintype "bidirectional"))
      (node (ref "R121") (pin "1") (pinfunction "1_1") (pintype "passive"))
    )
    (net (code "28") (name "D3") (class "Default")
      (node (ref "PCB1") (pin "28") (pinfunction "28_28") (pintype "bidirectional"))
      (node (ref "R123") (pin "1") (pinfunction "1_1") (pintype "passive"))
    )
    (net (code "29") (name "D4") (class "Default")
      (node (ref "PCB1") (pin "14") (pinfunction "14(TX3)_14") (pintype "bidirectional"))
      (node (ref "R125") (pin "1") (pinfunction "1_1") (pintype "passive"))
    )
    (net (code "30") (name "D5") (class "Default")
      (node (ref "PCB1") (pin "15") (pinfunction "15(RX3)_15") (pintype "bidirectional"))
      (node (ref "R127") (pin "1") (pinfunction "1_1") (pintype "passive"))
    )
    (net (code "31") (name "D6") (class "Default")
      (node (ref "PCB1") (pin "29") (pinfunction "29_29") (pintype "bidirectional"))
      (node (ref "R129") (pin "1") (pinfunction "1_1") (pintype "passive"))
    )
    (net (code "32") (name "D7") (class "Default")
      (node (ref "PCB1") (pin "11") (pinfunction "11_11") (pintype "bidirectional"))
      (node (ref "R131") (pin "1") (pinfunction "1_1") (pintype "passive"))
    )
    (net (code "33") (name "DEPOSIT") (class "Default")
      (node (ref "PCB1") (pin "A4") (pinfunction "A4_A4") (pintype "bidirectional"))
      (node (ref "S10") (pin "P1") (pinfunction "P1_P1") (pintype "bidirectional"))
    )
    (net (code "34") (name "DEPOSIT_NEXT") (class "Default")
      (node (ref "PCB1") (pin "A5") (pinfunction "A5_A5") (pintype "bidirectional"))
      (node (ref "S10") (pin "P3") (pinfunction "P3_P3") (pintype "bidirectional"))
    )
    (net (code "35") (name "DUE_RESET") (class "Default")
      (node (ref "C100") (pin "+") (pinfunction "+_+") (pintype "passive"))
      (node (ref "PCB1") (pin "RESET") (pinfunction "RESET_RESET") (pintype "bidirectional"))
    )
    (net (code "36") (name "EXAMINE") (class "Default")
      (node (ref "PCB1") (pin "A2") (pinfunction "A2_A2") (pintype "bidirectional"))
      (node (ref "S9") (pin "P1") (pinfunction "P1_P1") (pintype "bidirectional"))
    )
    (net (code "37") (name "EXAMINE_NEXT") (class "Default")
      (node (ref "PCB1") (pin "A3") (pinfunction "A3_A3") (pintype "bidirectional"))
      (node (ref "S9") (pin "P3") (pinfunction "P3_P3") (pintype "bidirectional"))
    )
    (net (code "38") (name "GND") (class "Default")
      (node (ref "J1") (pin "2") (pinfunction "2_2") (pintype "passive"))
      (node (ref "J2") (pin "3") (pinfunction "3_3") (pintype "passive"))
      (node (ref "J2") (pin "7") (pinfunction "7_7") (pintype "passive"))
      (node (ref "PCB1") (pin "GND") (pinfunction "GND_GND") (pintype "bidirectional"))
      (node (ref "PCB1") (pin "GND.") (pinfunction "GND._GND.") (pintype "bidirectional"))
      (node (ref "PCB1") (pin "GND..") (pinfunction "GND.._GND..") (pintype "bidirectional"))
      (node (ref "PCB1") (pin "GND...") (pinfunction "GND..._GND...") (pintype "bidirectional"))
      (node (ref "PCB1") (pin "GND....") (pinfunction "GND...._GND....") (pintype "bidirectional"))
      (node (ref "PCB1") (pin "GND__") (pinfunction "GND___GND__") (pintype "bidirectional"))
      (node (ref "R100") (pin "1") (pinfunction "1_1") (pintype "passive"))
      (node (ref "R101") (pin "2") (pinfunction "2_2") (pintype "passive"))
      (node (ref "R102") (pin "2") (pinfunction "2_2") (pintype "passive"))
      (node (ref "R103") (pin "2") (pinfunction "2_2") (pintype "passive"))
      (node (ref "R104") (pin "2") (pinfunction "2_2") (pintype "passive"))
      (node (ref "R105") (pin "2") (pinfunction "2_2") (pintype "passive"))
      (node (ref "R106") (pin "2") (pinfunction "2_2") (pintype "passive"))
      (node (ref "R107") (pin "2") (pinfunction "2_2") (pintype "passive"))
      (node (ref "R108") (pin "2") (pinfunction "2_2") (pintype "passive"))
      (node (ref "R109") (pin "2") (pinfunction "2_2") (pintype "passive"))
      (node (ref "R110") (pin "2") (pinfunction "2_2") (pintype "passive"))
      (node (ref "R111") (pin "2") (pinfunction "2_2") (pintype "passive"))
      (node (ref "R112") (pin "2") (pinfunction "2_2") (pintype "passive"))
      (node (ref "R113") (pin "2") (pinfunction "2_2") (pintype "passive"))
      (node (ref "R114") (pin "2") (pinfunction "2_2") (pintype "passive"))
      (node (ref "R115") (pin "2") (pinfunction "2_2") (pintype "passive"))
      (node (ref "R116") (pin "2") (pinfunction "2_2") (pintype "passive"))
      (node (ref "S10") (pin "P2") (pinfunction "P2_P2") (pintype "bidirectional"))
      (node (ref "S11") (pin "P2") (pinfunction "P2_P2") (pintype "bidirectional"))
      (node (ref "S12") (pin "P2") (pinfunction "P2_P2") (pintype "bidirectional"))
      (node (ref "S13") (pin "P2") (pinfunction "P2_P2") (pintype "bidirectional"))
      (node (ref "S14") (pin "P2") (pinfunction "P2_P2") (pintype "bidirectional"))
      (node (ref "S7") (pin "P2") (pinfunction "P2_P2") (pintype "bidirectional"))
      (node (ref "S8") (pin "P2") (pinfunction "P2_P2") (pintype "bidirectional"))
      (node (ref "S9") (pin "P2") (pinfunction "P2_P2") (pintype "bidirectional"))
      (node (ref "U100") (pin "9") (pinfunction "GND_9") (pintype "passive"))
      (node (ref "U101") (pin "9") (pinfunction "GND_9") (pintype "passive"))
      (node (ref "U102") (pin "9") (pinfunction "GND_9") (pintype "passive"))
      (node (ref "U103") (pin "9") (pinfunction "GND_9") (pintype "passive"))
      (node (ref "U104") (pin "9") (pinfunction "GND_9") (pintype "passive"))
    )
    (net (code "39") (name "HLDA") (class "Default")
      (node (ref "PCB1") (pin "22") (pinfunction "22_22") (pintype "bidirectional"))
      (node (ref "R150") (pin "1") (pinfunction "1_1") (pintype "passive"))
    )
    (net (code "40") (name "HLTA") (class "Default")
      (node (ref "PCB1") (pin "5") (pinfunction "5_5") (pintype "bidirectional"))
      (node (ref "R141") (pin "1") (pinfunction "1_1") (pintype "passive"))
    )
    (net (code "41") (name "INP") (class "Default")
      (node (ref "PCB1") (pin "8") (pinfunction "8_8") (pintype "bidirectional"))
      (node (ref "R146") (pin "1") (pinfunction "1_1") (pintype "passive"))
    )
    (net (code "42") (name "INT") (class "Default")
      (node (ref "PCB1") (pin "2") (pinfunction "2_2") (pintype "bidirectional"))
      (node (ref "R135") (pin "1") (pinfunction "1_1") (pintype "passive"))
    )
    (net (code "43") (name "INTE") (class "Default")
      (node (ref "PCB1") (pin "12") (pinfunction "12_12") (pintype "bidirectional"))
      (node (ref "R151") (pin "1") (pinfunction "1_1") (pintype "passive"))
    )
    (net (code "44") (name "IOREF") (class "Default")
      (node (ref "PCB1") (pin "I/OREF") (pinfunction "IOREF_I/OREF") (pintype "bidirectional"))
    )
    (net (code "45") (name "M1") (class "Default")
      (node (ref "PCB1") (pin "7") (pinfunction "7_7") (pintype "bidirectional"))
      (node (ref "R145") (pin "1") (pinfunction "1_1") (pintype "passive"))
    )
    (net (code "46") (name "MEMR") (class "Default")
      (node (ref "PCB1") (pin "9") (pinfunction "9_9") (pintype "bidirectional"))
      (node (ref "R148") (pin "1") (pinfunction "1_1") (pintype "passive"))
    )
    (net (code "47") (name "MISO") (class "Default")
      (node (ref "J2") (pin "5") (pinfunction "5_5") (pintype "passive"))
      (node (ref "PCB1") (pin "MISO") (pinfunction "MISO_MISO") (pintype "bidirectional"))
    )
    (net (code "48") (name "MOSI") (class "Default")
      (node (ref "J2") (pin "6") (pinfunction "6_6") (pintype "passive"))
      (node (ref "PCB1") (pin "MOSI") (pinfunction "MOSI_MOSI") (pintype "bidirectional"))
    )
    (net (code "49") (name "Net-(C100-Pad-)") (class "Default")
      (node (ref "C100") (pin "-") (pinfunction "-_-") (pintype "passive"))
      (node (ref "R100") (pin "2") (pinfunction "2_2") (pintype "passive"))
    )
    (net (code "50") (name "Net-(LED1-PadC)") (class "Default")
      (node (ref "LED1") (pin "C") (pinfunction "C_C") (pintype "passive"))
      (node (ref "R181") (pin "2") (pinfunction "2_2") (pintype "passive"))
    )
    (net (code "51") (name "Net-(LED2-PadC)") (class "Default")
      (node (ref "LED2") (pin "C") (pinfunction "C_C") (pintype "passive"))
      (node (ref "R180") (pin "2") (pinfunction "2_2") (pintype "passive"))
    )
    (net (code "52") (name "Net-(LED3-PadC)") (class "Default")
      (node (ref "LED3") (pin "C") (pinfunction "C_C") (pintype "passive"))
      (node (ref "R178") (pin "2") (pinfunction "2_2") (pintype "passive"))
    )
    (net (code "53") (name "Net-(LED4-PadC)") (class "Default")
      (node (ref "LED4") (pin "C") (pinfunction "C_C") (pintype "passive"))
      (node (ref "R176") (pin "2") (pinfunction "2_2") (pintype "passive"))
    )
    (net (code "54") (name "Net-(LED5-PadC)") (class "Default")
      (node (ref "LED5") (pin "C") (pinfunction "C_C") (pintype "passive"))
      (node (ref "R175") (pin "2") (pinfunction "2_2") (pintype "passive"))
    )
    (net (code "55") (name "Net-(LED6-PadC)") (class "Default")
      (node (ref "LED6") (pin "C") (pinfunction "C_C") (pintype "passive"))
      (node (ref "R173") (pin "2") (pinfunction "2_2") (pintype "passive"))
    )
    (net (code "56") (name "Net-(LED7-PadC)") (class "Default")
      (node (ref "LED7") (pin "C") (pinfunction "C_C") (pintype "passive"))
      (node (ref "R171") (pin "2") (pinfunction "2_2") (pintype "passive"))
    )
    (net (code "57") (name "Net-(LED8-PadC)") (class "Default")
      (node (ref "LED8") (pin "C") (pinfunction "C_C") (pintype "passive"))
      (node (ref "R169") (pin "2") (pinfunction "2_2") (pintype "passive"))
    )
    (net (code "58") (name "Net-(LED9-PadC)") (class "Default")
      (node (ref "LED9") (pin "C") (pinfunction "C_C") (pintype "passive"))
      (node (ref "R167") (pin "2") (pinfunction "2_2") (pintype "passive"))
    )
    (net (code "59") (name "Net-(LED10-PadC)") (class "Default")
      (node (ref "LED10") (pin "C") (pinfunction "C_C") (pintype "passive"))
      (node (ref "R165") (pin "2") (pinfunction "2_2") (pintype "passive"))
    )
    (net (code "60") (name "Net-(LED11-PadC)") (class "Default")
      (node (ref "LED11") (pin "C") (pinfunction "C_C") (pintype "passive"))
      (node (ref "R161") (pin "2") (pinfunction "2_2") (pintype "passive"))
    )
    (net (code "61") (name "Net-(LED12-PadC)") (class "Default")
      (node (ref "LED12") (pin "C") (pinfunction "C_C") (pintype "passive"))
      (node (ref "R159") (pin "2") (pinfunction "2_2") (pintype "passive"))
    )
    (net (code "62") (name "Net-(LED13-PadC)") (class "Default")
      (node (ref "LED13") (pin "C") (pinfunction "C_C") (pintype "passive"))
      (node (ref "R157") (pin "2") (pinfunction "2_2") (pintype "passive"))
    )
    (net (code "63") (name "Net-(LED14-PadC)") (class "Default")
      (node (ref "LED14") (pin "C") (pinfunction "C_C") (pintype "passive"))
      (node (ref "R155") (pin "2") (pinfunction "2_2") (pintype "passive"))
    )
    (net (code "64") (name "Net-(LED15-PadC)") (class "Default")
      (node (ref "LED15") (pin "C") (pinfunction "C_C") (pintype "passive"))
      (node (ref "R153") (pin "1") (pinfunction "1_1") (pintype "passive"))
    )
    (net (code "65") (name "Net-(LED16-PadC)") (class "Default")
      (node (ref "LED16") (pin "C") (pinfunction "C_C") (pintype "passive"))
      (node (ref "R187") (pin "1") (pinfunction "1_1") (pintype "passive"))
    )
    (net (code "66") (name "Net-(LED17-PadC)") (class "Default")
      (node (ref "LED17") (pin "C") (pinfunction "C_C") (pintype "passive"))
      (node (ref "R185") (pin "1") (pinfunction "1_1") (pintype "passive"))
    )
    (net (code "67") (name "Net-(LED18-PadC)") (class "Default")
      (node (ref "LED18") (pin "C") (pinfunction "C_C") (pintype "passive"))
      (node (ref "R183") (pin "1") (pinfunction "1_1") (pintype "passive"))
    )
    (net (code "68") (name "Net-(LED19-PadC)") (class "Default")
      (node (ref "LED19") (pin "C") (pinfunction "C_C") (pintype "passive"))
      (node (ref "R182") (pin "2") (pinfunction "2_2") (pintype "passive"))
    )
    (net (code "69") (name "Net-(LED20-PadC)") (class "Default")
      (node (ref "LED20") (pin "C") (pinfunction "C_C") (pintype "passive"))
      (node (ref "R179") (pin "2") (pinfunction "2_2") (pintype "passive"))
    )
    (net (code "70") (name "Net-(LED21-PadC)") (class "Default")
      (node (ref "LED21") (pin "C") (pinfunction "C_C") (pintype "passive"))
      (node (ref "R177") (pin "2") (pinfunction "2_2") (pintype "passive"))
    )
    (net (code "71") (name "Net-(LED22-PadC)") (class "Default")
      (node (ref "LED22") (pin "C") (pinfunction "C_C") (pintype "passive"))
      (node (ref "R174") (pin "2") (pinfunction "2_2") (pintype "passive"))
    )
    (net (code "72") (name "Net-(LED23-PadC)") (class "Default")
      (node (ref "LED23") (pin "C") (pinfunction "C_C") (pintype "passive"))
      (node (ref "R172") (pin "2") (pinfunction "2_2") (pintype "passive"))
    )
    (net (code "73") (name "Net-(LED24-PadC)") (class "Default")
      (node (ref "LED24") (pin "C") (pinfunction "C_C") (pintype "passive"))
      (node (ref "R170") (pin "2") (pinfunction "2_2") (pintype "passive"))
    )
    (net (code "74") (name "Net-(LED25-PadC)") (class "Default")
      (node (ref "LED25") (pin "C") (pinfunction "C_C") (pintype "passive"))
      (node (ref "R168") (pin "2") (pinfunction "2_2") (pintype "passive"))
    )
    (net (code "75") (name "Net-(LED26-PadC)") (class "Default")
      (node (ref "LED26") (pin "C") (pinfunction "C_C") (pintype "passive"))
      (node (ref "R166") (pin "2") (pinfunction "2_2") (pintype "passive"))
    )
    (net (code "76") (name "Net-(LED27-PadC)") (class "Default")
      (node (ref "LED27") (pin "C") (pinfunction "C_C") (pintype "passive"))
      (node (ref "R164") (pin "2") (pinfunction "2_2") (pintype "passive"))
    )
    (net (code "77") (name "Net-(LED28-PadC)") (class "Default")
      (node (ref "LED28") (pin "C") (pinfunction "C_C") (pintype "passive"))
      (node (ref "R163") (pin "2") (pinfunction "2_2") (pintype "passive"))
    )
    (net (code "78") (name "Net-(LED29-PadC)") (class "Default")
      (node (ref "LED29") (pin "C") (pinfunction "C_C") (pintype "passive"))
      (node (ref "R162") (pin "2") (pinfunction "2_2") (pintype "passive"))
    )
    (net (code "79") (name "Net-(LED30-PadC)") (class "Default")
      (node (ref "LED30") (pin "C") (pinfunction "C_C") (pintype "passive"))
      (node (ref "R160") (pin "2") (pinfunction "2_2") (pintype "passive"))
    )
    (net (code "80") (name "Net-(LED31-PadC)") (class "Default")
      (node (ref "LED31") (pin "C") (pinfunction "C_C") (pintype "passive"))
      (node (ref "R158") (pin "2") (pinfunction "2_2") (pintype "passive"))
    )
    (net (code "81") (name "Net-(LED32-PadC)") (class "Default")
      (node (ref "LED32") (pin "C") (pinfunction "C_C") (pintype "passive"))
      (node (ref "R156") (pin "2") (pinfunction "2_2") (pintype "passive"))
    )
    (net (code "82") (name "Net-(LED33-PadC)") (class "Default")
      (node (ref "LED33") (pin "C") (pinfunction "C_C") (pintype "passive"))
      (node (ref "R154") (pin "1") (pinfunction "1_1") (pintype "passive"))
    )
    (net (code "83") (name "Net-(LED34-PadC)") (class "Default")
      (node (ref "LED34") (pin "C") (pinfunction "C_C") (pintype "passive"))
      (node (ref "R188") (pin "1") (pinfunction "1_1") (pintype "passive"))
    )
    (net (code "84") (name "Net-(LED35-PadC)") (class "Default")
      (node (ref "LED35") (pin "C") (pinfunction "C_C") (pintype "passive"))
      (node (ref "R186") (pin "1") (pinfunction "1_1") (pintype "passive"))
    )
    (net (code "85") (name "Net-(LED36-PadC)") (class "Default")
      (node (ref "LED36") (pin "C") (pinfunction "C_C") (pintype "passive"))
      (node (ref "R184") (pin "1") (pinfunction "1_1") (pintype "passive"))
    )
    (net (code "86") (name "Net-(U100-1B)") (class "Default")
      (node (ref "R117") (pin "2") (pinfunction "2_2") (pintype "passive"))
      (node (ref "U100") (pin "1") (pinfunction "1B_1") (pintype "input"))
    )
    (net (code "87") (name "Net-(U100-1C)") (class "Default")
      (node (ref "R183") (pin "2") (pinfunction "2_2") (pintype "passive"))
      (node (ref "U100") (pin "18") (pinfunction "1C_18") (pintype "output"))
    )
    (net (code "88") (name "Net-(U100-2B)") (class "Default")
      (node (ref "R118") (pin "2") (pinfunction "2_2") (pintype "passive"))
      (node (ref "U100") (pin "2") (pinfunction "2B_2") (pintype "input"))
    )
    (net (code "89") (name "Net-(U100-2C)") (class "Default")
      (node (ref "R184") (pin "2") (pinfunction "2_2") (pintype "passive"))
      (node (ref "U100") (pin "17") (pinfunction "2C_17") (pintype "output"))
    )
    (net (code "90") (name "Net-(U100-3B)") (class "Default")
      (node (ref "R119") (pin "2") (pinfunction "2_2") (pintype "passive"))
      (node (ref "U100") (pin "3") (pinfunction "3B_3") (pintype "input"))
    )
    (net (code "91") (name "Net-(U100-3C)") (class "Default")
      (node (ref "R185") (pin "2") (pinfunction "2_2") (pintype "passive"))
      (node (ref "U100") (pin "16") (pinfunction "3C_16") (pintype "output"))
    )
    (net (code "92") (name "Net-(U100-4B)") (class "Default")
      (node (ref "R120") (pin "2") (pinfunction "2_2") (pintype "passive"))
      (node (ref "U100") (pin "4") (pinfunction "4B_4") (pintype "input"))
    )
    (net (code "93") (name "Net-(U100-4C)") (class "Default")
      (node (ref "R186") (pin "2") (pinfunction "2_2") (pintype "passive"))
      (node (ref "U100") (pin "15") (pinfunction "4C_15") (pintype "output"))
    )
    (net (code "94") (name "Net-(U100-5B)") (class "Default")
      (node (ref "R121") (pin "2") (pinfunction "2_2") (pintype "passive"))
      (node (ref "U100") (pin "5") (pinfunction "5B_5") (pintype "input"))
    )
    (net (code "95") (name "Net-(U100-5C)") (class "Default")
      (node (ref "R187") (pin "2") (pinfunction "2_2") (pintype "passive"))
      (node (ref "U100") (pin "14") (pinfunction "5C_14") (pintype "output"))
    )
    (net (code "96") (name "Net-(U100-6B)") (class "Default")
      (node (ref "R122") (pin "2") (pinfunction "2_2") (pintype "passive"))
      (node (ref "U100") (pin "6") (pinfunction "6B_6") (pintype "input"))
    )
    (net (code "97") (name "Net-(U100-6C)") (class "Default")
      (node (ref "R188") (pin "2") (pinfunction "2_2") (pintype "passive"))
      (node (ref "U100") (pin "13") (pinfunction "6C_13") (pintype "output"))
    )
    (net (code "98") (name "Net-(U100-7B)") (class "Default")
      (node (ref "R123") (pin "2") (pinfunction "2_2") (pintype "passive"))
      (node (ref "U100") (pin "7") (pinfunction "7B_7") (pintype "input"))
    )
    (net (code "99") (name "Net-(U100-7C)") (class "Default")
      (node (ref "R153") (pin "2") (pinfunction "2_2") (pintype "passive"))
      (node (ref "U100") (pin "12") (pinfunction "7C_12") (pintype "output"))
    )
    (net (code "100") (name "Net-(U100-8B)") (class "Default")
      (node (ref "R124") (pin "2") (pinfunction "2_2") (pintype "passive"))
      (node (ref "U100") (pin "8") (pinfunction "8B_8") (pintype "input"))
    )
    (net (code "101") (name "Net-(U100-8C)") (class "Default")
      (node (ref "R154") (pin "2") (pinfunction "2_2") (pintype "passive"))
      (node (ref "U100") (pin "11") (pinfunction "8C_11") (pintype "output"))
    )
    (net (code "102") (name "Net-(U101-1B)") (class "Default")
      (node (ref "R125") (pin "2") (pinfunction "2_2") (pintype "passive"))
      (node (ref "U101") (pin "1") (pinfunction "1B_1") (pintype "input"))
    )
    (net (code "103") (name "Net-(U101-1C)") (class "Default")
      (node (ref "R155") (pin "1") (pinfunction "1_1") (pintype "passive"))
      (node (ref "U101") (pin "18") (pinfunction "1C_18") (pintype "output"))
    )
    (net (code "104") (name "Net-(U101-2B)") (class "Default")
      (node (ref "R126") (pin "2") (pinfunction "2_2") (pintype "passive"))
      (node (ref "U101") (pin "2") (pinfunction "2B_2") (pintype "input"))
    )
    (net (code "105") (name "Net-(U101-2C)") (class "Default")
      (node (ref "R156") (pin "1") (pinfunction "1_1") (pintype "passive"))
      (node (ref "U101") (pin "17") (pinfunction "2C_17") (pintype "output"))
    )
    (net (code "106") (name "Net-(U101-3B)") (class "Default")
      (node (ref "R127") (pin "2") (pinfunction "2_2") (pintype "passive"))
      (node (ref "U101") (pin "3") (pinfunction "3B_3") (pintype "input"))
    )
    (net (code "107") (name "Net-(U101-3C)") (class "Default")
      (node (ref "R157") (pin "1") (pinfunction "1_1") (pintype "passive"))
      (node (ref "U101") (pin "16") (pinfunction "3C_16") (pintype "output"))
    )
    (net (code "108") (name "Net-(U101-4B)") (class "Default")
      (node (ref "R128") (pin "2") (pinfunction "2_2") (pintype "passive"))
      (node (ref "U101") (pin "4") (pinfunction "4B_4") (pintype "input"))
    )
    (net (code "109") (name "Net-(U101-4C)") (class "Default")
      (node (ref "R158") (pin "1") (pinfunction "1_1") (pintype "passive"))
      (node (ref "U101") (pin "15") (pinfunction "4C_15") (pintype "output"))
    )
    (net (code "110") (name "Net-(U101-5B)") (class "Default")
      (node (ref "R129") (pin "2") (pinfunction "2_2") (pintype "passive"))
      (node (ref "U101") (pin "5") (pinfunction "5B_5") (pintype "input"))
    )
    (net (code "111") (name "Net-(U101-5C)") (class "Default")
      (node (ref "R159") (pin "1") (pinfunction "1_1") (pintype "passive"))
      (node (ref "U101") (pin "14") (pinfunction "5C_14") (pintype "output"))
    )
    (net (code "112") (name "Net-(U101-6B)") (class "Default")
      (node (ref "R130") (pin "2") (pinfunction "2_2") (pintype "passive"))
      (node (ref "U101") (pin "6") (pinfunction "6B_6") (pintype "input"))
    )
    (net (code "113") (name "Net-(U101-6C)") (class "Default")
      (node (ref "R160") (pin "1") (pinfunction "1_1") (pintype "passive"))
      (node (ref "U101") (pin "13") (pinfunction "6C_13") (pintype "output"))
    )
    (net (code "114") (name "Net-(U101-7B)") (class "Default")
      (node (ref "R131") (pin "2") (pinfunction "2_2") (pintype "passive"))
      (node (ref "U101") (pin "7") (pinfunction "7B_7") (pintype "input"))
    )
    (net (code "115") (name "Net-(U101-7C)") (class "Default")
      (node (ref "R161") (pin "1") (pinfunction "1_1") (pintype "passive"))
      (node (ref "U101") (pin "12") (pinfunction "7C_12") (pintype "output"))
    )
    (net (code "116") (name "Net-(U101-8B)") (class "Default")
      (node (ref "R132") (pin "2") (pinfunction "2_2") (pintype "passive"))
      (node (ref "U101") (pin "8") (pinfunction "8B_8") (pintype "input"))
    )
    (net (code "117") (name "Net-(U101-8C)") (class "Default")
      (node (ref "R162") (pin "1") (pinfunction "1_1") (pintype "passive"))
      (node (ref "U101") (pin "11") (pinfunction "8C_11") (pintype "output"))
    )
    (net (code "118") (name "Net-(U102-1B)") (class "Default")
      (node (ref "R133") (pin "2") (pinfunction "2_2") (pintype "passive"))
      (node (ref "U102") (pin "1") (pinfunction "1B_1") (pintype "input"))
    )
    (net (code "119") (name "Net-(U102-1C)") (class "Default")
      (node (ref "R163") (pin "1") (pinfunction "1_1") (pintype "passive"))
      (node (ref "U102") (pin "18") (pinfunction "1C_18") (pintype "output"))
    )
    (net (code "120") (name "Net-(U102-2B)") (class "Default")
      (node (ref "R134") (pin "2") (pinfunction "2_2") (pintype "passive"))
      (node (ref "U102") (pin "2") (pinfunction "2B_2") (pintype "input"))
    )
    (net (code "121") (name "Net-(U102-2C)") (class "Default")
      (node (ref "R164") (pin "1") (pinfunction "1_1") (pintype "passive"))
      (node (ref "U102") (pin "17") (pinfunction "2C_17") (pintype "output"))
    )
    (net (code "122") (name "Net-(U102-3B)") (class "Default")
      (node (ref "R135") (pin "2") (pinfunction "2_2") (pintype "passive"))
      (node (ref "U102") (pin "3") (pinfunction "3B_3") (pintype "input"))
    )
    (net (code "123") (name "Net-(U102-3C)") (class "Default")
      (node (ref "R165") (pin "1") (pinfunction "1_1") (pintype "passive"))
      (node (ref "U102") (pin "16") (pinfunction "3C_16") (pintype "output"))
    )
    (net (code "124") (name "Net-(U102-4B)") (class "Default")
      (node (ref "R136") (pin "2") (pinfunction "2_2") (pintype "passive"))
      (node (ref "U102") (pin "4") (pinfunction "4B_4") (pintype "input"))
    )
    (net (code "125") (name "Net-(U102-4C)") (class "Default")
      (node (ref "R166") (pin "1") (pinfunction "1_1") (pintype "passive"))
      (node (ref "U102") (pin "15") (pinfunction "4C_15") (pintype "output"))
    )
    (net (code "126") (name "Net-(U103-1B)") (class "Default")
      (node (ref "R137") (pin "2") (pinfunction "2_2") (pintype "passive"))
      (node (ref "U103") (pin "1") (pinfunction "1B_1") (pintype "input"))
    )
    (net (code "127") (name "Net-(U103-1C)") (class "Default")
      (node (ref "R167") (pin "1") (pinfunction "1_1") (pintype "passive"))
      (node (ref "U103") (pin "18") (pinfunction "1C_18") (pintype "output"))
    )
    (net (code "128") (name "Net-(U103-2B)") (class "Default")
      (node (ref "R138") (pin "2") (pinfunction "2_2") (pintype "passive"))
      (node (ref "U103") (pin "2") (pinfunction "2B_2") (pintype "input"))
    )
    (net (code "129") (name "Net-(U103-2C)") (class "Default")
      (node (ref "R168") (pin "1") (pinfunction "1_1") (pintype "passive"))
      (node (ref "U103") (pin "17") (pinfunction "2C_17") (pintype "output"))
    )
    (net (code "130") (name "Net-(U103-3B)") (class "Default")
      (node (ref "R139") (pin "2") (pinfunction "2_2") (pintype "passive"))
      (node (ref "U103") (pin "3") (pinfunction "3B_3") (pintype "input"))
    )
    (net (code "131") (name "Net-(U103-3C)") (class "Default")
      (node (ref "R169") (pin "1") (pinfunction "1_1") (pintype "passive"))
      (node (ref "U103") (pin "16") (pinfunction "3C_16") (pintype "output"))
    )
    (net (code "132") (name "Net-(U103-4B)") (class "Default")
      (node (ref "R140") (pin "2") (pinfunction "2_2") (pintype "passive"))
      (node (ref "U103") (pin "4") (pinfunction "4B_4") (pintype "input"))
    )
    (net (code "133") (name "Net-(U103-4C)") (class "Default")
      (node (ref "R170") (pin "1") (pinfunction "1_1") (pintype "passive"))
      (node (ref "U103") (pin "15") (pinfunction "4C_15") (pintype "output"))
    )
    (net (code "134") (name "Net-(U103-5B)") (class "Default")
      (node (ref "R141") (pin "2") (pinfunction "2_2") (pintype "passive"))
      (node (ref "U103") (pin "5") (pinfunction "5B_5") (pintype "input"))
    )
    (net (code "135") (name "Net-(U103-5C)") (class "Default")
      (node (ref "R171") (pin "1") (pinfunction "1_1") (pintype "passive"))
      (node (ref "U103") (pin "14") (pinfunction "5C_14") (pintype "output"))
    )
    (net (code "136") (name "Net-(U103-6B)") (class "Default")
      (node (ref "R142") (pin "2") (pinfunction "2_2") (pintype "passive"))
      (node (ref "U103") (pin "6") (pinfunction "6B_6") (pintype "input"))
    )
    (net (code "137") (name "Net-(U103-6C)") (class "Default")
      (node (ref "R172") (pin "1") (pinfunction "1_1") (pintype "passive"))
      (node (ref "U103") (pin "13") (pinfunction "6C_13") (pintype "output"))
    )
    (net (code "138") (name "Net-(U103-7B)") (class "Default")
      (node (ref "R143") (pin "2") (pinfunction "2_2") (pintype "passive"))
      (node (ref "U103") (pin "7") (pinfunction "7B_7") (pintype "input"))
    )
    (net (code "139") (name "Net-(U103-7C)") (class "Default")
      (node (ref "R173") (pin "1") (pinfunction "1_1") (pintype "passive"))
      (node (ref "U103") (pin "12") (pinfunction "7C_12") (pintype "output"))
    )
    (net (code "140") (name "Net-(U103-8B)") (class "Default")
      (node (ref "R144") (pin "2") (pinfunction "2_2") (pintype "passive"))
      (node (ref "U103") (pin "8") (pinfunction "8B_8") (pintype "input"))
    )
    (net (code "141") (name "Net-(U103-8C)") (class "Default")
      (node (ref "R174") (pin "1") (pinfunction "1_1") (pintype "passive"))
      (node (ref "U103") (pin "11") (pinfunction "8C_11") (pintype "output"))
    )
    (net (code "142") (name "Net-(U104-1B)") (class "Default")
      (node (ref "R145") (pin "2") (pinfunction "2_2") (pintype "passive"))
      (node (ref "U104") (pin "1") (pinfunction "1B_1") (pintype "input"))
    )
    (net (code "143") (name "Net-(U104-1C)") (class "Default")
      (node (ref "R175") (pin "1") (pinfunction "1_1") (pintype "passive"))
      (node (ref "U104") (pin "18") (pinfunction "1C_18") (pintype "output"))
    )
    (net (code "144") (name "Net-(U104-2B)") (class "Default")
      (node (ref "R146") (pin "2") (pinfunction "2_2") (pintype "passive"))
      (node (ref "U104") (pin "2") (pinfunction "2B_2") (pintype "input"))
    )
    (net (code "145") (name "Net-(U104-2C)") (class "Default")
      (node (ref "R176") (pin "1") (pinfunction "1_1") (pintype "passive"))
      (node (ref "U104") (pin "17") (pinfunction "2C_17") (pintype "output"))
    )
    (net (code "146") (name "Net-(U104-3B)") (class "Default")
      (node (ref "R147") (pin "2") (pinfunction "2_2") (pintype "passive"))
      (node (ref "U104") (pin "3") (pinfunction "3B_3") (pintype "input"))
    )
    (net (code "147") (name "Net-(U104-3C)") (class "Default")
      (node (ref "R177") (pin "1") (pinfunction "1_1") (pintype "passive"))
      (node (ref "U104") (pin "16") (pinfunction "3C_16") (pintype "output"))
    )
    (net (code "148") (name "Net-(U104-4B)") (class "Default")
      (node (ref "R148") (pin "2") (pinfunction "2_2") (pintype "passive"))
      (node (ref "U104") (pin "4") (pinfunction "4B_4") (pintype "input"))
    )
    (net (code "149") (name "Net-(U104-4C)") (class "Default")
      (node (ref "R178") (pin "1") (pinfunction "1_1") (pintype "passive"))
      (node (ref "U104") (pin "15") (pinfunction "4C_15") (pintype "output"))
    )
    (net (code "150") (name "Net-(U104-5B)") (class "Default")
      (node (ref "R149") (pin "2") (pinfunction "2_2") (pintype "passive"))
      (node (ref "U104") (pin "5") (pinfunction "5B_5") (pintype "input"))
    )
    (net (code "151") (name "Net-(U104-5C)") (class "Default")
      (node (ref "R179") (pin "1") (pinfunction "1_1") (pintype "passive"))
      (node (ref "U104") (pin "14") (pinfunction "5C_14") (pintype "output"))
    )
    (net (code "152") (name "Net-(U104-6B)") (class "Default")
      (node (ref "R150") (pin "2") (pinfunction "2_2") (pintype "passive"))
      (node (ref "U104") (pin "6") (pinfunction "6B_6") (pintype "input"))
    )
    (net (code "153") (name "Net-(U104-6C)") (class "Default")
      (node (ref "R180") (pin "1") (pinfunction "1_1") (pintype "passive"))
      (node (ref "U104") (pin "13") (pinfunction "6C_13") (pintype "output"))
    )
    (net (code "154") (name "Net-(U104-7B)") (class "Default")
      (node (ref "R151") (pin "2") (pinfunction "2_2") (pintype "passive"))
      (node (ref "U104") (pin "7") (pinfunction "7B_7") (pintype "input"))
    )
    (net (code "155") (name "Net-(U104-7C)") (class "Default")
      (node (ref "R181") (pin "1") (pinfunction "1_1") (pintype "passive"))
      (node (ref "U104") (pin "12") (pinfunction "7C_12") (pintype "output"))
    )
    (net (code "156") (name "Net-(U104-8B)") (class "Default")
      (node (ref "R152") (pin "2") (pinfunction "2_2") (pintype "passive"))
      (node (ref "U104") (pin "8") (pinfunction "8B_8") (pintype "input"))
    )
    (net (code "157") (name "Net-(U104-8C)") (class "Default")
      (node (ref "R182") (pin "1") (pinfunction "1_1") (pintype "passive"))
      (node (ref "U104") (pin "11") (pinfunction "8C_11") (pintype "output"))
    )
    (net (code "158") (name "OUT") (class "Default")
      (node (ref "PCB1") (pin "6") (pinfunction "6_6") (pintype "bidirectional"))
      (node (ref "R143") (pin "1") (pinfunction "1_1") (pintype "passive"))
    )
    (net (code "159") (name "PROT") (class "Default")
      (node (ref "PCB1") (pin "13") (pinfunction "13_13") (pintype "bidirectional"))
      (node (ref "R149") (pin "1") (pinfunction "1_1") (pintype "passive"))
    )
    (net (code "160") (name "PROTECT") (class "Default")
      (node (ref "PCB1") (pin "A6") (pinfunction "A6_A6") (pintype "bidirectional"))
      (node (ref "S12") (pin "P1") (pinfunction "P1_P1") (pintype "bidirectional"))
    )
    (net (code "161") (name "RESET") (class "Default")
      (node (ref "PCB1") (pin "52") (pinfunction "52_52") (pintype "bidirectional"))
      (node (ref "S11") (pin "P1") (pinfunction "P1_P1") (pintype "bidirectional"))
    )
    (net (code "162") (name "RUN") (class "Default")
      (node (ref "PCB1") (pin "20") (pinfunction "20(SDA)_20") (pintype "bidirectional"))
      (node (ref "S7") (pin "P3") (pinfunction "P3_P3") (pintype "bidirectional"))
    )
    (net (code "163") (name "SCK") (class "Default")
      (node (ref "J2") (pin "4") (pinfunction "4_4") (pintype "passive"))
      (node (ref "PCB1") (pin "SCK") (pinfunction "SCK_SCK") (pintype "bidirectional"))
    )
    (net (code "164") (name "SERIAL_RX") (class "Default")
      (node (ref "J1") (pin "3") (pinfunction "3_3") (pintype "passive"))
      (node (ref "PCB1") (pin "19") (pinfunction "19(RX1)_19") (pintype "bidirectional"))
    )
    (net (code "165") (name "SERIAL_TX") (class "Default")
      (node (ref "J1") (pin "4") (pinfunction "4_4") (pintype "passive"))
      (node (ref "PCB1") (pin "18") (pinfunction "18(TX1)_18") (pintype "bidirectional"))
    )
    (net (code "166") (name "SLOW") (class "Default")
      (node (ref "PCB1") (pin "A1") (pinfunction "A1_A1") (pintype "bidirectional"))
      (node (ref "S8") (pin "P3") (pinfunction "P3_P3") (pintype "bidirectional"))
    )
    (net (code "167") (name "STACK") (class "Default")
      (node (ref "PCB1") (pin "4") (pinfunction "4_4") (pintype "bidirectional"))
      (node (ref "R139") (pin "1") (pinfunction "1_1") (pintype "passive"))
    )
    (net (code "168") (name "STEP") (class "Default")
      (node (ref "PCB1") (pin "A0") (pinfunction "A0_A0") (pintype "bidirectional"))
      (node (ref "S8") (pin "P1") (pinfunction "P1_P1") (pintype "bidirectional"))
    )
    (net (code "169") (name "STOP") (class "Default")
      (node (ref "PCB1") (pin "21") (pinfunction "21(SCL)_21") (pintype "bidirectional"))
      (node (ref "S7") (pin "P1") (pinfunction "P1_P1") (pintype "bidirectional"))
    )
    (net (code "170") (name "SW0") (class "Default")
      (node (ref "PCB1") (pin "A8") (pinfunction "A8_A8") (pintype "bidirectional"))
      (node (ref "R101") (pin "1") (pinfunction "1_1") (pintype "passive"))
      (node (ref "S6") (pin "3") (pinfunction "3_3") (pintype "passive"))
    )
    (net (code "171") (name "SW1") (class "Default")
      (node (ref "PCB1") (pin "A9") (pinfunction "A9_A9") (pintype "bidirectional"))
      (node (ref "R102") (pin "1") (pinfunction "1_1") (pintype "passive"))
      (node (ref "S6") (pin "2") (pinfunction "2_2") (pintype "passive"))
    )
    (net (code "172") (name "SW2") (class "Default")
      (node (ref "PCB1") (pin "A10") (pinfunction "A10_A10") (pintype "bidirectional"))
      (node (ref "R103") (pin "1") (pinfunction "1_1") (pintype "passive"))
      (node (ref "S6") (pin "1") (pinfunction "1_1") (pintype "passive"))
    )
    (net (code "173") (name "SW3") (class "Default")
      (node (ref "PCB1") (pin "A11") (pinfunction "A11_A11") (pintype "bidirectional"))
      (node (ref "R104") (pin "1") (pinfunction "1_1") (pintype "passive"))
      (node (ref "S5") (pin "3") (pinfunction "3_3") (pintype "passive"))
    )
    (net (code "174") (name "SW4") (class "Default")
      (node (ref "PCB1") (pin "A12") (pinfunction "A12_A12") (pintype "bidirectional"))
      (node (ref "R105") (pin "1") (pinfunction "1_1") (pintype "passive"))
      (node (ref "S5") (pin "2") (pinfunction "2_2") (pintype "passive"))
    )
    (net (code "175") (name "SW5") (class "Default")
      (node (ref "PCB1") (pin "A13") (pinfunction "A13_A13") (pintype "bidirectional"))
      (node (ref "R106") (pin "1") (pinfunction "1_1") (pintype "passive"))
      (node (ref "S5") (pin "1") (pinfunction "1_1") (pintype "passive"))
    )
    (net (code "176") (name "SW6") (class "Default")
      (node (ref "PCB1") (pin "A14") (pinfunction "A14_A14") (pintype "bidirectional"))
      (node (ref "R107") (pin "1") (pinfunction "1_1") (pintype "passive"))
      (node (ref "S4") (pin "3") (pinfunction "3_3") (pintype "passive"))
    )
    (net (code "177") (name "SW7") (class "Default")
      (node (ref "PCB1") (pin "A15") (pinfunction "A15_A15") (pintype "bidirectional"))
      (node (ref "R108") (pin "1") (pinfunction "1_1") (pintype "passive"))
      (node (ref "S4") (pin "2") (pinfunction "2_2") (pintype "passive"))
    )
    (net (code "178") (name "SW8") (class "Default")
      (node (ref "PCB1") (pin "17") (pinfunction "17(RX2)_17") (pintype "bidirectional"))
      (node (ref "R109") (pin "1") (pinfunction "1_1") (pintype "passive"))
      (node (ref "S4") (pin "1") (pinfunction "1_1") (pintype "passive"))
    )
    (net (code "179") (name "SW9") (class "Default")
      (node (ref "PCB1") (pin "16") (pinfunction "16(TX2)_16") (pintype "bidirectional"))
      (node (ref "R110") (pin "1") (pinfunction "1_1") (pintype "passive"))
      (node (ref "S3") (pin "3") (pinfunction "3_3") (pintype "passive"))
    )
    (net (code "180") (name "SW10") (class "Default")
      (node (ref "PCB1") (pin "23") (pinfunction "23_23") (pintype "bidirectional"))
      (node (ref "R111") (pin "1") (pinfunction "1_1") (pintype "passive"))
      (node (ref "S3") (pin "2") (pinfunction "2_2") (pintype "passive"))
    )
    (net (code "181") (name "SW11") (class "Default")
      (node (ref "PCB1") (pin "24") (pinfunction "24_24") (pintype "bidirectional"))
      (node (ref "R112") (pin "1") (pinfunction "1_1") (pintype "passive"))
      (node (ref "S3") (pin "1") (pinfunction "1_1") (pintype "passive"))
    )
    (net (code "182") (name "SW12") (class "Default")
      (node (ref "PCB1") (pin "SDA1") (pinfunction "SDA1_SDA1") (pintype "bidirectional"))
      (node (ref "R113") (pin "1") (pinfunction "1_1") (pintype "passive"))
      (node (ref "S2") (pin "3") (pinfunction "3_3") (pintype "passive"))
    )
    (net (code "183") (name "SW13") (class "Default")
      (node (ref "PCB1") (pin "SCL1") (pinfunction "SCL1_SCL1") (pintype "bidirectional"))
      (node (ref "R114") (pin "1") (pinfunction "1_1") (pintype "passive"))
      (node (ref "S2") (pin "2") (pinfunction "2_2") (pintype "passive"))
    )
    (net (code "184") (name "SW14") (class "Default")
      (node (ref "PCB1") (pin "42") (pinfunction "42_42") (pintype "bidirectional"))
      (node (ref "R115") (pin "1") (pinfunction "1_1") (pintype "passive"))
      (node (ref "S2") (pin "1") (pinfunction "1_1") (pintype "passive"))
    )
    (net (code "185") (name "SW15") (class "Default")
      (node (ref "PCB1") (pin "43") (pinfunction "43_43") (pintype "bidirectional"))
      (node (ref "R116") (pin "1") (pinfunction "1_1") (pintype "passive"))
      (node (ref "S1") (pin "1") (pinfunction "1_1") (pintype "passive"))
    )
    (net (code "186") (name "UNPROTECT") (class "Default")
      (node (ref "PCB1") (pin "A7") (pinfunction "A7_A7") (pintype "bidirectional"))
      (node (ref "S12") (pin "P3") (pinfunction "P3_P3") (pintype "bidirectional"))
    )
    (net (code "187") (name "VCC") (class "Default")
      (node (ref "PCB1") (pin "3.3V") (pinfunction "3.3V_3.3V") (pintype "bidirectional"))
      (node (ref "S1") (pin "2") (pinfunction "2_2") (pintype "passive"))
      (node (ref "S2") (pin "4") (pinfunction "4_4") (pintype "passive"))
      (node (ref "S2") (pin "5") (pinfunction "5_5") (pintype "passive"))
      (node (ref "S2") (pin "6") (pinfunction "6_6") (pintype "passive"))
      (node (ref "S3") (pin "4") (pinfunction "4_4") (pintype "passive"))
      (node (ref "S3") (pin "5") (pinfunction "5_5") (pintype "passive"))
      (node (ref "S3") (pin "6") (pinfunction "6_6") (pintype "passive"))
      (node (ref "S4") (pin "4") (pinfunction "4_4") (pintype "passive"))
      (node (ref "S4") (pin "5") (pinfunction "5_5") (pintype "passive"))
      (node (ref "S4") (pin "6") (pinfunction "6_6") (pintype "passive"))
      (node (ref "S5") (pin "4") (pinfunction "4_4") (pintype "passive"))
      (node (ref "S5") (pin "5") (pinfunction "5_5") (pintype "passive"))
      (node (ref "S5") (pin "6") (pinfunction "6_6") (pintype "passive"))
      (node (ref "S6") (pin "4") (pinfunction "4_4") (pintype "passive"))
      (node (ref "S6") (pin "5") (pinfunction "5_5") (pintype "passive"))
      (node (ref "S6") (pin "6") (pinfunction "6_6") (pintype "passive"))
    )
    (net (code "188") (name "VIN") (class "Default")
      (node (ref "PCB1") (pin "VIN") (pinfunction "VIN_VIN") (pintype "bidirectional"))
    )
    (net (code "189") (name "WAIT") (class "Default")
      (node (ref "PCB1") (pin "10") (pinfunction "10_10") (pintype "bidirectional"))
      (node (ref "R152") (pin "1") (pinfunction "1_1") (pintype "passive"))
    )
    (net (code "190") (name "WO") (class "Default")
      (node (ref "PCB1") (pin "3") (pinfunction "3_3") (pintype "bidirectional"))
      (node (ref "R137") (pin "1") (pinfunction "1_1") (pintype "passive"))
    )
    (net (code "191") (name "unconnected-(J1-Pad5)") (class "Default")
      (node (ref "J1") (pin "5") (pinfunction "5_5") (pintype "passive"))
    )
    (net (code "192") (name "unconnected-(J1-Pad6)") (class "Default")
      (node (ref "J1") (pin "6") (pinfunction "6_6") (pintype "passive"))
    )
    (net (code "193") (name "unconnected-(J2-Pad2)") (class "Default")
      (node (ref "J2") (pin "2") (pinfunction "2_2") (pintype "passive"))
    )
    (net (code "194") (name "unconnected-(J2-Pad8)") (class "Default")
      (node (ref "J2") (pin "8") (pinfunction "8_8") (pintype "passive"))
    )
    (net (code "195") (name "unconnected-(PCB1-(N{slash}C)-PadN{slash}C)") (class "Default")
      (node (ref "PCB1") (pin "N/C") (pinfunction "(N/C)_N/C") (pintype "bidirectional"))
    )
    (net (code "196") (name "unconnected-(PCB1-0(RX)-Pad0)") (class "Default")
      (node (ref "PCB1") (pin "0") (pinfunction "0(RX)_0") (pintype "bidirectional"))
    )
    (net (code "197") (name "unconnected-(PCB1-1(TX)-Pad1)") (class "Default")
      (node (ref "PCB1") (pin "1") (pinfunction "1(TX)_1") (pintype "bidirectional"))
    )
    (net (code "198") (name "unconnected-(PCB1-PadRESET.)") (class "Default")
      (node (ref "PCB1") (pin "RESET.") (pinfunction "RESET._RESET.") (pintype "bidirectional"))
    )
    (net (code "199") (name "unconnected-(U102-5B-Pad5)") (class "Default")
      (node (ref "U102") (pin "5") (pinfunction "5B_5") (pintype "input"))
    )
    (net (code "200") (name "unconnected-(U102-5C-Pad14)") (class "Default")
      (node (ref "U102") (pin "14") (pinfunction "5C_14") (pintype "output"))
    )
    (net (code "201") (name "unconnected-(U102-6B-Pad6)") (class "Default")
      (node (ref "U102") (pin "6") (pinfunction "6B_6") (pintype "input"))
    )
    (net (code "202") (name "unconnected-(U102-6C-Pad13)") (class "Default")
      (node (ref "U102") (pin "13") (pinfunction "6C_13") (pintype "output"))
    )
    (net (code "203") (name "unconnected-(U102-7B-Pad7)") (class "Default")
      (node (ref "U102") (pin "7") (pinfunction "7B_7") (pintype "input"))
    )
    (net (code "204") (name "unconnected-(U102-7C-Pad12)") (class "Default")
      (node (ref "U102") (pin "12") (pinfunction "7C_12") (pintype "output"))
    )
    (net (code "205") (name "unconnected-(U102-8B-Pad8)") (class "Default")
      (node (ref "U102") (pin "8") (pinfunction "8B_8") (pintype "input"))
    )
    (net (code "206") (name "unconnected-(U102-8C-Pad11)") (class "Default")
      (node (ref "U102") (pin "11") (pinfunction "8C_11") (pintype "output"))
    )
  )
)
